# ccnor_stm32_v20.net
KiCad netlist of a schematic drawn in EAGLE
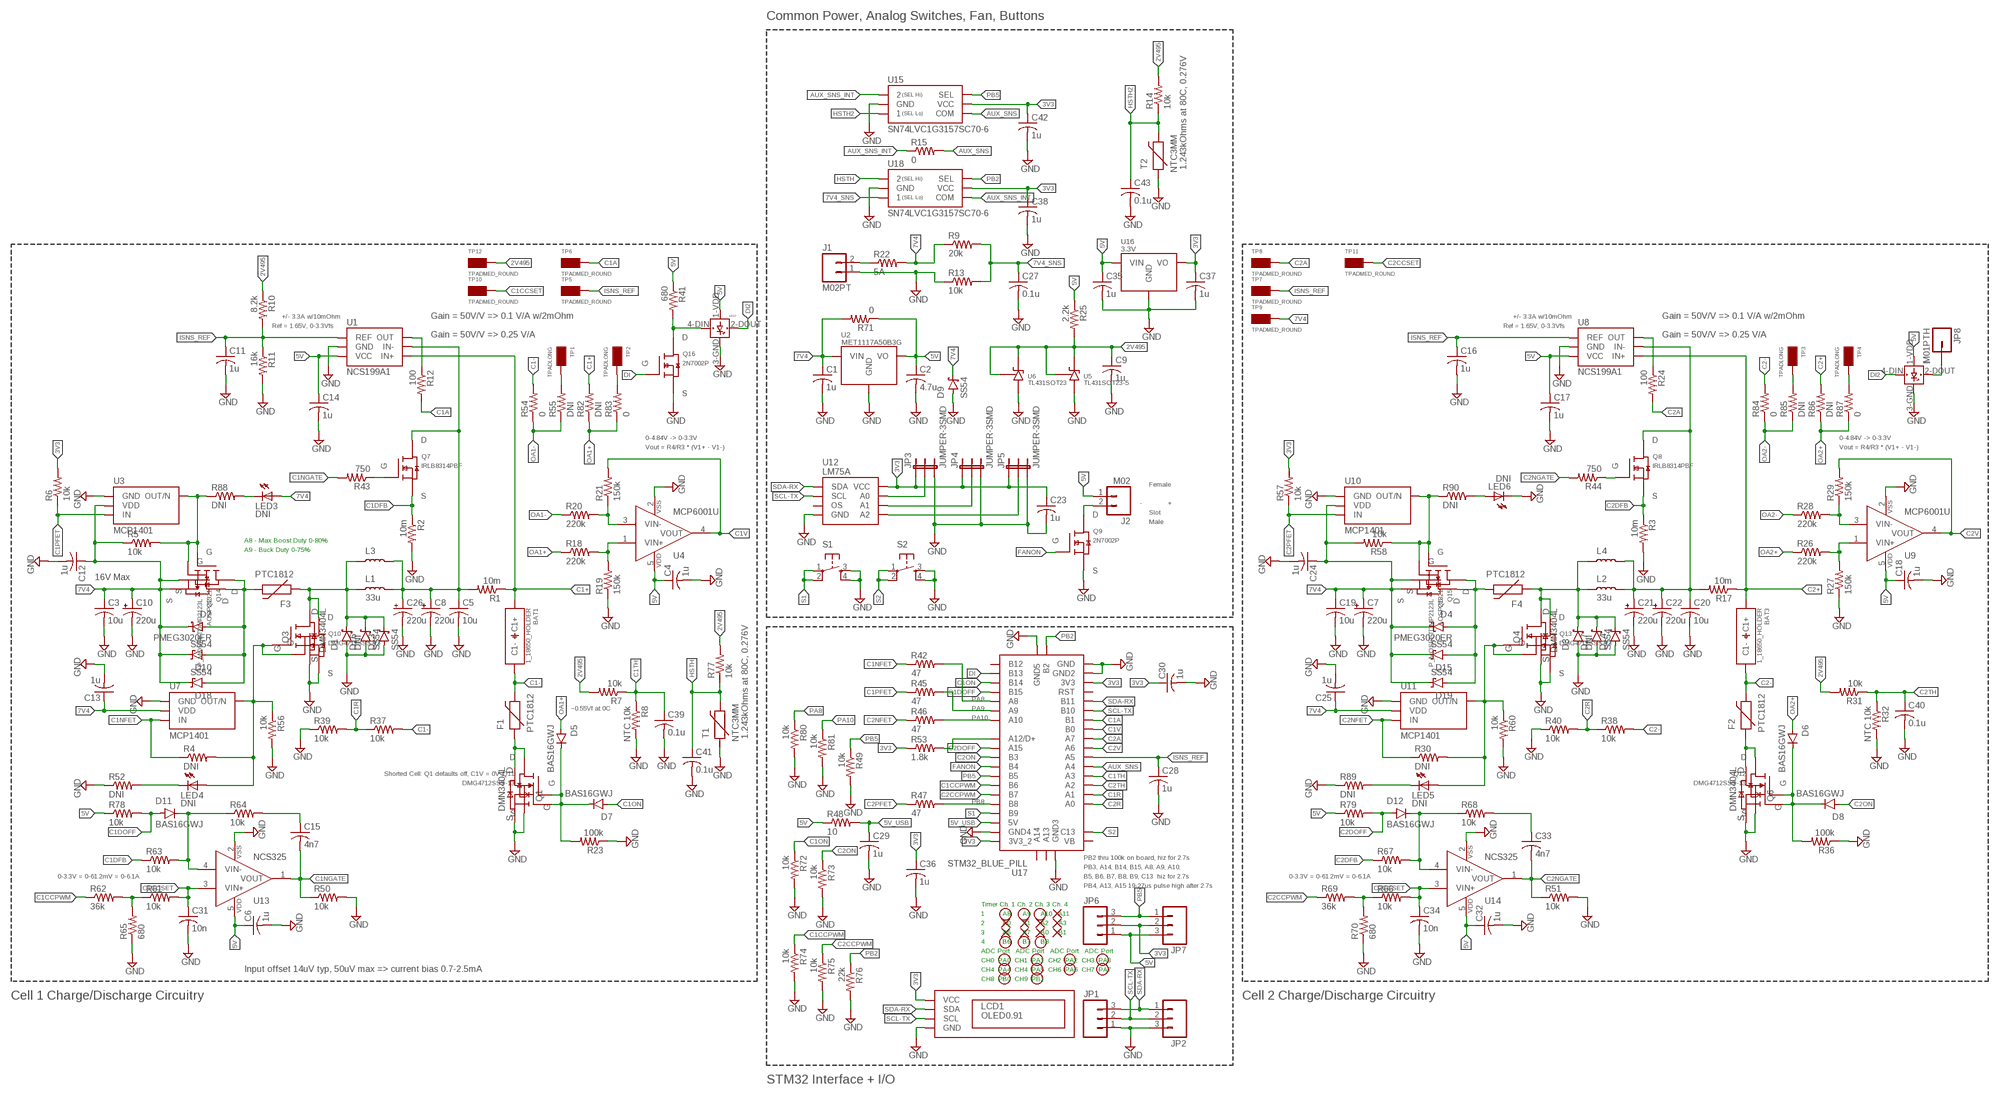
[diagram p0: schematic, sheet 1]

(export (version "E")
  (design (tool "Eeschema 10.0.6"))
  (components
    (comp (ref "BAT1")
      (value "1_18650_HOLDER")
      (footprint "eagle-import:1S_18650_SMD_NH")
      (libsource (lib "eagle-import") (part "1_18650_HOLDER"))
    )
    (comp (ref "BAT3")
      (value "1_18650_HOLDER")
      (footprint "eagle-import:1S_18650_SMD_NH")
      (libsource (lib "eagle-import") (part "1_18650_HOLDER"))
    )
    (comp (ref "C1")
      (value "1u")
      (footprint "eagle-import:C0402")
      (libsource (lib "eagle-import") (part "C-USC0402"))
    )
    (comp (ref "C2")
      (value "4.7u")
      (footprint "eagle-import:C0402")
      (libsource (lib "eagle-import") (part "C-USC0402"))
    )
    (comp (ref "C3")
      (value "10u")
      (footprint "eagle-import:C1206")
      (libsource (lib "eagle-import") (part "C-USC1206"))
    )
    (comp (ref "C4")
      (value "1u")
      (footprint "eagle-import:C0402")
      (libsource (lib "eagle-import") (part "C-USC0402"))
    )
    (comp (ref "C5")
      (value "10u")
      (footprint "eagle-import:C1206")
      (libsource (lib "eagle-import") (part "C-USC1206"))
    )
    (comp (ref "C6")
      (value "1u")
      (footprint "eagle-import:C0402")
      (libsource (lib "eagle-import") (part "C-USC0402"))
    )
    (comp (ref "C7")
      (value "220u")
      (footprint "eagle-import:PANASONIC_D")
      (libsource (lib "eagle-import") (part "CPOL-USD"))
    )
    (comp (ref "C8")
      (value "220u")
      (footprint "eagle-import:PANASONIC_D")
      (libsource (lib "eagle-import") (part "CPOL-USD"))
    )
    (comp (ref "C9")
      (value "1u")
      (footprint "eagle-import:C0402")
      (libsource (lib "eagle-import") (part "C-USC0402"))
    )
    (comp (ref "C10")
      (value "220u")
      (footprint "eagle-import:PANASONIC_D")
      (libsource (lib "eagle-import") (part "CPOL-USD"))
    )
    (comp (ref "C11")
      (value "1u")
      (footprint "eagle-import:C0402")
      (libsource (lib "eagle-import") (part "C-USC0402"))
    )
    (comp (ref "C12")
      (value "1u")
      (footprint "eagle-import:C0402")
      (libsource (lib "eagle-import") (part "C-USC0402"))
    )
    (comp (ref "C13")
      (value "1u")
      (footprint "eagle-import:C0402")
      (libsource (lib "eagle-import") (part "C-USC0402"))
    )
    (comp (ref "C14")
      (value "1u")
      (footprint "eagle-import:C0402")
      (libsource (lib "eagle-import") (part "C-USC0402"))
    )
    (comp (ref "C15")
      (value "4n7")
      (footprint "eagle-import:C0402")
      (libsource (lib "eagle-import") (part "C-USC0402"))
    )
    (comp (ref "C16")
      (value "1u")
      (footprint "eagle-import:C0402")
      (libsource (lib "eagle-import") (part "C-USC0402"))
    )
    (comp (ref "C17")
      (value "1u")
      (footprint "eagle-import:C0402")
      (libsource (lib "eagle-import") (part "C-USC0402"))
    )
    (comp (ref "C18")
      (value "1u")
      (footprint "eagle-import:C0402")
      (libsource (lib "eagle-import") (part "C-USC0402"))
    )
    (comp (ref "C19")
      (value "10u")
      (footprint "eagle-import:C1206")
      (libsource (lib "eagle-import") (part "C-USC1206"))
    )
    (comp (ref "C20")
      (value "10u")
      (footprint "eagle-import:C1206")
      (libsource (lib "eagle-import") (part "C-USC1206"))
    )
    (comp (ref "C21")
      (value "220u")
      (footprint "eagle-import:PANASONIC_D")
      (libsource (lib "eagle-import") (part "CPOL-USD"))
    )
    (comp (ref "C22")
      (value "220u")
      (footprint "eagle-import:PANASONIC_D")
      (libsource (lib "eagle-import") (part "CPOL-USD"))
    )
    (comp (ref "C23")
      (value "1u")
      (footprint "eagle-import:C0402")
      (libsource (lib "eagle-import") (part "C-USC0402"))
    )
    (comp (ref "C24")
      (value "1u")
      (footprint "eagle-import:C0402")
      (libsource (lib "eagle-import") (part "C-USC0402"))
    )
    (comp (ref "C25")
      (value "1u")
      (footprint "eagle-import:C0402")
      (libsource (lib "eagle-import") (part "C-USC0402"))
    )
    (comp (ref "C26")
      (value "220u")
      (footprint "eagle-import:PANASONIC_D")
      (libsource (lib "eagle-import") (part "CPOL-USD"))
    )
    (comp (ref "C27")
      (value "0.1u")
      (footprint "eagle-import:C0402")
      (libsource (lib "eagle-import") (part "C-USC0402"))
    )
    (comp (ref "C28")
      (value "1u")
      (footprint "eagle-import:C0402")
      (libsource (lib "eagle-import") (part "C-USC0402"))
    )
    (comp (ref "C29")
      (value "1u")
      (footprint "eagle-import:C0402")
      (libsource (lib "eagle-import") (part "C-USC0402"))
    )
    (comp (ref "C30")
      (value "1u")
      (footprint "eagle-import:C0402")
      (libsource (lib "eagle-import") (part "C-USC0402"))
    )
    (comp (ref "C31")
      (value "10n")
      (footprint "eagle-import:C0402")
      (libsource (lib "eagle-import") (part "C-USC0402"))
    )
    (comp (ref "C32")
      (value "1u")
      (footprint "eagle-import:C0402")
      (libsource (lib "eagle-import") (part "C-USC0402"))
    )
    (comp (ref "C33")
      (value "4n7")
      (footprint "eagle-import:C0402")
      (libsource (lib "eagle-import") (part "C-USC0402"))
    )
    (comp (ref "C34")
      (value "10n")
      (footprint "eagle-import:C0402")
      (libsource (lib "eagle-import") (part "C-USC0402"))
    )
    (comp (ref "C35")
      (value "1u")
      (footprint "eagle-import:C0402")
      (libsource (lib "eagle-import") (part "C-USC0402"))
    )
    (comp (ref "C36")
      (value "1u")
      (footprint "eagle-import:C0402")
      (libsource (lib "eagle-import") (part "C-USC0402"))
    )
    (comp (ref "C37")
      (value "1u")
      (footprint "eagle-import:C0402")
      (libsource (lib "eagle-import") (part "C-USC0402"))
    )
    (comp (ref "C38")
      (value "1u")
      (footprint "eagle-import:C0402")
      (libsource (lib "eagle-import") (part "C-USC0402"))
    )
    (comp (ref "C39")
      (value "0.1u")
      (footprint "eagle-import:C0402")
      (libsource (lib "eagle-import") (part "C-USC0402"))
    )
    (comp (ref "C40")
      (value "0.1u")
      (footprint "eagle-import:C0402")
      (libsource (lib "eagle-import") (part "C-USC0402"))
    )
    (comp (ref "C41")
      (value "0.1u")
      (footprint "eagle-import:C0402")
      (libsource (lib "eagle-import") (part "C-USC0402"))
    )
    (comp (ref "C42")
      (value "1u")
      (footprint "eagle-import:C0402")
      (libsource (lib "eagle-import") (part "C-USC0402"))
    )
    (comp (ref "C43")
      (value "0.1u")
      (footprint "eagle-import:C0402")
      (libsource (lib "eagle-import") (part "C-USC0402"))
    )
    (comp (ref "D1")
      (value "DNI")
      (footprint "eagle-import:SOD123W")
      (libsource (lib "eagle-import") (part "PMEG3020ER"))
    )
    (comp (ref "D2")
      (value "PMEG3020ER")
      (footprint "eagle-import:SOD123W")
      (libsource (lib "eagle-import") (part "PMEG3020ER"))
    )
    (comp (ref "D3")
      (value "DNI")
      (footprint "eagle-import:SOD123W")
      (libsource (lib "eagle-import") (part "PMEG3020ER"))
    )
    (comp (ref "D4")
      (value "PMEG3020ER")
      (footprint "eagle-import:SOD123W")
      (libsource (lib "eagle-import") (part "PMEG3020ER"))
    )
    (comp (ref "D5")
      (value "BAS16GWJ")
      (footprint "eagle-import:SOD323")
      (libsource (lib "eagle-import") (part "BAT60A"))
    )
    (comp (ref "D6")
      (value "BAS16GWJ")
      (footprint "eagle-import:SOD323")
      (libsource (lib "eagle-import") (part "BAT60A"))
    )
    (comp (ref "D7")
      (value "BAS16GWJ")
      (footprint "eagle-import:SOD323")
      (libsource (lib "eagle-import") (part "BAT60A"))
    )
    (comp (ref "D8")
      (value "BAS16GWJ")
      (footprint "eagle-import:SOD323")
      (libsource (lib "eagle-import") (part "BAT60A"))
    )
    (comp (ref "D9")
      (value "SS54")
      (footprint "eagle-import:SMA")
      (libsource (lib "eagle-import") (part "SS54"))
    )
    (comp (ref "D10")
      (value "SS54")
      (footprint "eagle-import:SMA")
      (libsource (lib "eagle-import") (part "SS54"))
    )
    (comp (ref "D11")
      (value "BAS16GWJ")
      (footprint "eagle-import:SOD323")
      (libsource (lib "eagle-import") (part "BAT60A"))
    )
    (comp (ref "D12")
      (value "BAS16GWJ")
      (footprint "eagle-import:SOD323")
      (libsource (lib "eagle-import") (part "BAT60A"))
    )
    (comp (ref "D13")
      (value "SS54")
      (footprint "eagle-import:SMA")
      (libsource (lib "eagle-import") (part "SS54"))
    )
    (comp (ref "D14")
      (value "SS54")
      (footprint "eagle-import:SMA")
      (libsource (lib "eagle-import") (part "SS54"))
    )
    (comp (ref "D15")
      (value "SS54")
      (footprint "eagle-import:SMA")
      (libsource (lib "eagle-import") (part "SS54"))
    )
    (comp (ref "D16")
      (value "SS54")
      (footprint "eagle-import:SMA")
      (libsource (lib "eagle-import") (part "SS54"))
    )
    (comp (ref "D17")
      (value "SS54")
      (footprint "eagle-import:SMA")
      (libsource (lib "eagle-import") (part "SS54"))
    )
    (comp (ref "D18")
      (value "SS54")
      (footprint "eagle-import:SMA")
      (libsource (lib "eagle-import") (part "SS54"))
    )
    (comp (ref "D19")
      (value "SS54")
      (footprint "eagle-import:SMA")
      (libsource (lib "eagle-import") (part "SS54"))
    )
    (comp (ref "F1")
      (value "PTC1812")
      (footprint "eagle-import:1812")
      (libsource (lib "eagle-import") (part "PTC1812"))
    )
    (comp (ref "F2")
      (value "PTC1812")
      (footprint "eagle-import:1812")
      (libsource (lib "eagle-import") (part "PTC1812"))
    )
    (comp (ref "F3")
      (value "PTC1812")
      (footprint "eagle-import:1812")
      (libsource (lib "eagle-import") (part "PTC1812"))
    )
    (comp (ref "F4")
      (value "PTC1812")
      (footprint "eagle-import:1812")
      (libsource (lib "eagle-import") (part "PTC1812"))
    )
    (comp (ref "J1")
      (value "M02PT")
      (footprint "eagle-import:PHOENIXCONTACT1935161")
      (libsource (lib "eagle-import") (part "M02PT"))
    )
    (comp (ref "J2")
      (value "M02")
      (footprint "eagle-import:B2B-XH-A")
      (libsource (lib "eagle-import") (part "M02"))
    )
    (comp (ref "JP1")
      (value "M03PTH")
      (footprint "eagle-import:1X03")
      (libsource (lib "eagle-import") (part "M03PTH"))
    )
    (comp (ref "JP2")
      (value "M03PTH")
      (footprint "eagle-import:1X03")
      (libsource (lib "eagle-import") (part "M03PTH"))
    )
    (comp (ref "JP3")
      (value "JUMPER-3SMD")
      (footprint "eagle-import:SJ_3")
      (libsource (lib "eagle-import") (part "JUMPER-3SMD"))
    )
    (comp (ref "JP4")
      (value "JUMPER-3SMD")
      (footprint "eagle-import:SJ_3")
      (libsource (lib "eagle-import") (part "JUMPER-3SMD"))
    )
    (comp (ref "JP5")
      (value "JUMPER-3SMD")
      (footprint "eagle-import:SJ_3")
      (libsource (lib "eagle-import") (part "JUMPER-3SMD"))
    )
    (comp (ref "JP6")
      (value "M03PTH")
      (footprint "eagle-import:1X03")
      (libsource (lib "eagle-import") (part "M03PTH"))
    )
    (comp (ref "JP7")
      (value "M03PTH")
      (footprint "eagle-import:1X03")
      (libsource (lib "eagle-import") (part "M03PTH"))
    )
    (comp (ref "JP8")
      (value "M01PTH")
      (footprint "eagle-import:1X01")
      (libsource (lib "eagle-import") (part "M01PTH"))
    )
    (comp (ref "L1")
      (value "33u")
      (footprint "eagle-import:INDUCTOR_SMD_13MM")
      (libsource (lib "eagle-import") (part "SDR1307"))
    )
    (comp (ref "L2")
      (value "33u")
      (footprint "eagle-import:INDUCTOR_SMD_13MM")
      (libsource (lib "eagle-import") (part "SDR1307"))
    )
    (comp (ref "L3")
      (value "INDUCTOR6A-LG")
      (footprint "eagle-import:INDUCTOR_6A_8MMX15MM")
      (libsource (lib "eagle-import") (part "INDUCTOR6A-LG"))
    )
    (comp (ref "L4")
      (value "INDUCTOR6A-LG")
      (footprint "eagle-import:INDUCTOR_6A_8MMX15MM")
      (libsource (lib "eagle-import") (part "INDUCTOR6A-LG"))
    )
    (comp (ref "LCD1")
      (value "OLED0.91")
      (footprint "eagle-import:OLED0.91")
      (libsource (lib "eagle-import") (part "OLED0.91"))
    )
    (comp (ref "LED3")
      (value "DNI")
      (footprint "eagle-import:CHIPLED_0603")
      (libsource (lib "eagle-import") (part "LEDCHIPLED_0603"))
    )
    (comp (ref "LED4")
      (value "DNI")
      (footprint "eagle-import:CHIPLED_0603")
      (libsource (lib "eagle-import") (part "LEDCHIPLED_0603"))
    )
    (comp (ref "LED5")
      (value "DNI")
      (footprint "eagle-import:CHIPLED_0603")
      (libsource (lib "eagle-import") (part "LEDCHIPLED_0603"))
    )
    (comp (ref "LED6")
      (value "DNI")
      (footprint "eagle-import:CHIPLED_0603")
      (libsource (lib "eagle-import") (part "LEDCHIPLED_0603"))
    )
    (comp (ref "LED7")
      (value "WS2812B")
      (footprint "eagle-import:WS2812B")
      (libsource (lib "eagle-import") (part "WS2812B"))
    )
    (comp (ref "LED8")
      (value "WS2812B")
      (footprint "eagle-import:WS2812B")
      (libsource (lib "eagle-import") (part "WS2812B"))
    )
    (comp (ref "Q1")
      (value "DMN3404L")
      (footprint "eagle-import:SOT23")
      (libsource (lib "eagle-import") (part "DMN3404L"))
    )
    (comp (ref "Q2")
      (value "P_MOSFETDMP2123L")
      (footprint "eagle-import:SOT23")
      (libsource (lib "eagle-import") (part "P_MOSFETDMP2123L"))
    )
    (comp (ref "Q3")
      (value "DMN3404L")
      (footprint "eagle-import:SOT23")
      (libsource (lib "eagle-import") (part "DMN3404L"))
    )
    (comp (ref "Q4")
      (value "DMN3404L")
      (footprint "eagle-import:SOT23")
      (libsource (lib "eagle-import") (part "DMN3404L"))
    )
    (comp (ref "Q5")
      (value "P_MOSFETDMP2123L")
      (footprint "eagle-import:SOT23")
      (libsource (lib "eagle-import") (part "P_MOSFETDMP2123L"))
    )
    (comp (ref "Q6")
      (value "DMN3404L")
      (footprint "eagle-import:SOT23")
      (libsource (lib "eagle-import") (part "DMN3404L"))
    )
    (comp (ref "Q7")
      (value "IRLB8314PBF")
      (footprint "eagle-import:TO-220")
      (libsource (lib "eagle-import") (part "IRLB8314PBF"))
    )
    (comp (ref "Q8")
      (value "IRLB8314PBF")
      (footprint "eagle-import:TO-220")
      (libsource (lib "eagle-import") (part "IRLB8314PBF"))
    )
    (comp (ref "Q9")
      (value "2N7002P")
      (footprint "eagle-import:SOT23")
      (libsource (lib "eagle-import") (part "2N7002P"))
    )
    (comp (ref "Q10")
      (value "DMG4712SSS-13")
      (footprint "eagle-import:8-SOIC")
      (libsource (lib "eagle-import") (part "N-MOSFET-SOIC8"))
    )
    (comp (ref "Q11")
      (value "DMG4712SSS-13")
      (footprint "eagle-import:8-SOIC")
      (libsource (lib "eagle-import") (part "N-MOSFET-SOIC8"))
    )
    (comp (ref "Q12")
      (value "DMG4712SSS-13")
      (footprint "eagle-import:8-SOIC")
      (libsource (lib "eagle-import") (part "N-MOSFET-SOIC8"))
    )
    (comp (ref "Q13")
      (value "DMG4712SSS-13")
      (footprint "eagle-import:8-SOIC")
      (libsource (lib "eagle-import") (part "N-MOSFET-SOIC8"))
    )
    (comp (ref "Q14")
      (value "AOSP21321")
      (footprint "eagle-import:8-SOIC")
      (libsource (lib "eagle-import") (part "P-MOSFET-SOIC8"))
    )
    (comp (ref "Q15")
      (value "AOSP21321")
      (footprint "eagle-import:8-SOIC")
      (libsource (lib "eagle-import") (part "P-MOSFET-SOIC8"))
    )
    (comp (ref "Q16")
      (value "2N7002P")
      (footprint "eagle-import:SOT23")
      (libsource (lib "eagle-import") (part "2N7002P"))
    )
    (comp (ref "R1")
      (value "10m")
      (footprint "eagle-import:R1206")
      (libsource (lib "eagle-import") (part "R-US_R1206"))
    )
    (comp (ref "R2")
      (value "10m")
      (footprint "eagle-import:R1206")
      (libsource (lib "eagle-import") (part "R-US_R1206"))
    )
    (comp (ref "R3")
      (value "10m")
      (footprint "eagle-import:R1206")
      (libsource (lib "eagle-import") (part "R-US_R1206"))
    )
    (comp (ref "R4")
      (value "DNI")
      (footprint "eagle-import:R0402")
      (libsource (lib "eagle-import") (part "R-US_R0402"))
    )
    (comp (ref "R5")
      (value "10k")
      (footprint "eagle-import:R0402")
      (libsource (lib "eagle-import") (part "R-US_R0402"))
    )
    (comp (ref "R6")
      (value "10k")
      (footprint "eagle-import:R0402")
      (libsource (lib "eagle-import") (part "R-US_R0402"))
    )
    (comp (ref "R7")
      (value "10k")
      (footprint "eagle-import:R0402")
      (libsource (lib "eagle-import") (part "R-US_R0402"))
    )
    (comp (ref "R8")
      (value "NTC 10k")
      (footprint "eagle-import:R0402")
      (libsource (lib "eagle-import") (part "R-US_R0402"))
    )
    (comp (ref "R9")
      (value "20k")
      (footprint "eagle-import:R0402")
      (libsource (lib "eagle-import") (part "R-US_R0402"))
    )
    (comp (ref "R10")
      (value "8.2k")
      (footprint "eagle-import:R0402")
      (libsource (lib "eagle-import") (part "R-US_R0402"))
    )
    (comp (ref "R11")
      (value "16k")
      (footprint "eagle-import:R0402")
      (libsource (lib "eagle-import") (part "R-US_R0402"))
    )
    (comp (ref "R12")
      (value "100")
      (footprint "eagle-import:R0402")
      (libsource (lib "eagle-import") (part "R-US_R0402"))
    )
    (comp (ref "R13")
      (value "10k")
      (footprint "eagle-import:R0402")
      (libsource (lib "eagle-import") (part "R-US_R0402"))
    )
    (comp (ref "R14")
      (value "10k")
      (footprint "eagle-import:R0402")
      (libsource (lib "eagle-import") (part "R-US_R0402"))
    )
    (comp (ref "R15")
      (value "0")
      (footprint "eagle-import:R0402")
      (libsource (lib "eagle-import") (part "R-US_R0402"))
    )
    (comp (ref "R17")
      (value "10m")
      (footprint "eagle-import:R1206")
      (libsource (lib "eagle-import") (part "R-US_R1206"))
    )
    (comp (ref "R18")
      (value "220k")
      (footprint "eagle-import:R0402")
      (libsource (lib "eagle-import") (part "R-US_R0402"))
    )
    (comp (ref "R19")
      (value "150k")
      (footprint "eagle-import:R0402")
      (libsource (lib "eagle-import") (part "R-US_R0402"))
    )
    (comp (ref "R20")
      (value "220k")
      (footprint "eagle-import:R0402")
      (libsource (lib "eagle-import") (part "R-US_R0402"))
    )
    (comp (ref "R21")
      (value "150k")
      (footprint "eagle-import:R0402")
      (libsource (lib "eagle-import") (part "R-US_R0402"))
    )
    (comp (ref "R22")
      (value "5A")
      (footprint "eagle-import:R1206")
      (libsource (lib "eagle-import") (part "R-US_R1206"))
    )
    (comp (ref "R23")
      (value "100k")
      (footprint "eagle-import:R0402")
      (libsource (lib "eagle-import") (part "R-US_R0402"))
    )
    (comp (ref "R24")
      (value "100")
      (footprint "eagle-import:R0402")
      (libsource (lib "eagle-import") (part "R-US_R0402"))
    )
    (comp (ref "R25")
      (value "2.2k")
      (footprint "eagle-import:R0402")
      (libsource (lib "eagle-import") (part "R-US_R0402"))
    )
    (comp (ref "R26")
      (value "220k")
      (footprint "eagle-import:R0402")
      (libsource (lib "eagle-import") (part "R-US_R0402"))
    )
    (comp (ref "R27")
      (value "150k")
      (footprint "eagle-import:R0402")
      (libsource (lib "eagle-import") (part "R-US_R0402"))
    )
    (comp (ref "R28")
      (value "220k")
      (footprint "eagle-import:R0402")
      (libsource (lib "eagle-import") (part "R-US_R0402"))
    )
    (comp (ref "R29")
      (value "150k")
      (footprint "eagle-import:R0402")
      (libsource (lib "eagle-import") (part "R-US_R0402"))
    )
    (comp (ref "R30")
      (value "DNI")
      (footprint "eagle-import:R0402")
      (libsource (lib "eagle-import") (part "R-US_R0402"))
    )
    (comp (ref "R31")
      (value "10k")
      (footprint "eagle-import:R0402")
      (libsource (lib "eagle-import") (part "R-US_R0402"))
    )
    (comp (ref "R32")
      (value "NTC 10k")
      (footprint "eagle-import:R0402")
      (libsource (lib "eagle-import") (part "R-US_R0402"))
    )
    (comp (ref "R36")
      (value "100k")
      (footprint "eagle-import:R0402")
      (libsource (lib "eagle-import") (part "R-US_R0402"))
    )
    (comp (ref "R37")
      (value "10k")
      (footprint "eagle-import:R0402")
      (libsource (lib "eagle-import") (part "R-US_R0402"))
    )
    (comp (ref "R38")
      (value "10k")
      (footprint "eagle-import:R0402")
      (libsource (lib "eagle-import") (part "R-US_R0402"))
    )
    (comp (ref "R39")
      (value "10k")
      (footprint "eagle-import:R0402")
      (libsource (lib "eagle-import") (part "R-US_R0402"))
    )
    (comp (ref "R40")
      (value "10k")
      (footprint "eagle-import:R0402")
      (libsource (lib "eagle-import") (part "R-US_R0402"))
    )
    (comp (ref "R41")
      (value "680")
      (footprint "eagle-import:R0402")
      (libsource (lib "eagle-import") (part "R-US_R0402"))
    )
    (comp (ref "R42")
      (value "47")
      (footprint "eagle-import:R0402")
      (libsource (lib "eagle-import") (part "R-US_R0402"))
    )
    (comp (ref "R43")
      (value "750")
      (footprint "eagle-import:R0402")
      (libsource (lib "eagle-import") (part "R-US_R0402"))
    )
    (comp (ref "R44")
      (value "750")
      (footprint "eagle-import:R0402")
      (libsource (lib "eagle-import") (part "R-US_R0402"))
    )
    (comp (ref "R45")
      (value "47")
      (footprint "eagle-import:R0402")
      (libsource (lib "eagle-import") (part "R-US_R0402"))
    )
    (comp (ref "R46")
      (value "47")
      (footprint "eagle-import:R0402")
      (libsource (lib "eagle-import") (part "R-US_R0402"))
    )
    (comp (ref "R47")
      (value "47")
      (footprint "eagle-import:R0402")
      (libsource (lib "eagle-import") (part "R-US_R0402"))
    )
    (comp (ref "R48")
      (value "10")
      (footprint "eagle-import:R0402")
      (libsource (lib "eagle-import") (part "R-US_R0402"))
    )
    (comp (ref "R49")
      (value "10k")
      (footprint "eagle-import:R0402")
      (libsource (lib "eagle-import") (part "R-US_R0402"))
    )
    (comp (ref "R50")
      (value "10k")
      (footprint "eagle-import:R0402")
      (libsource (lib "eagle-import") (part "R-US_R0402"))
    )
    (comp (ref "R51")
      (value "10k")
      (footprint "eagle-import:R0402")
      (libsource (lib "eagle-import") (part "R-US_R0402"))
    )
    (comp (ref "R52")
      (value "DNI")
      (footprint "eagle-import:R0402")
      (libsource (lib "eagle-import") (part "R-US_R0402"))
    )
    (comp (ref "R53")
      (value "1.8k")
      (footprint "eagle-import:R0402")
      (libsource (lib "eagle-import") (part "R-US_R0402"))
    )
    (comp (ref "R54")
      (value "0")
      (footprint "eagle-import:R0402")
      (libsource (lib "eagle-import") (part "R-US_R0402"))
    )
    (comp (ref "R55")
      (value "DNI")
      (footprint "eagle-import:R0402")
      (libsource (lib "eagle-import") (part "R-US_R0402"))
    )
    (comp (ref "R56")
      (value "10k")
      (footprint "eagle-import:R0402")
      (libsource (lib "eagle-import") (part "R-US_R0402"))
    )
    (comp (ref "R57")
      (value "10k")
      (footprint "eagle-import:R0402")
      (libsource (lib "eagle-import") (part "R-US_R0402"))
    )
    (comp (ref "R58")
      (value "10k")
      (footprint "eagle-import:R0402")
      (libsource (lib "eagle-import") (part "R-US_R0402"))
    )
    (comp (ref "R60")
      (value "10k")
      (footprint "eagle-import:R0402")
      (libsource (lib "eagle-import") (part "R-US_R0402"))
    )
    (comp (ref "R61")
      (value "10k")
      (footprint "eagle-import:R0402")
      (libsource (lib "eagle-import") (part "R-US_R0402"))
    )
    (comp (ref "R62")
      (value "36k")
      (footprint "eagle-import:R0402")
      (libsource (lib "eagle-import") (part "R-US_R0402"))
    )
    (comp (ref "R63")
      (value "10k")
      (footprint "eagle-import:R0402")
      (libsource (lib "eagle-import") (part "R-US_R0402"))
    )
    (comp (ref "R64")
      (value "10k")
      (footprint "eagle-import:R0402")
      (libsource (lib "eagle-import") (part "R-US_R0402"))
    )
    (comp (ref "R65")
      (value "680")
      (footprint "eagle-import:R0402")
      (libsource (lib "eagle-import") (part "R-US_R0402"))
    )
    (comp (ref "R66")
      (value "10k")
      (footprint "eagle-import:R0402")
      (libsource (lib "eagle-import") (part "R-US_R0402"))
    )
    (comp (ref "R67")
      (value "10k")
      (footprint "eagle-import:R0402")
      (libsource (lib "eagle-import") (part "R-US_R0402"))
    )
    (comp (ref "R68")
      (value "10k")
      (footprint "eagle-import:R0402")
      (libsource (lib "eagle-import") (part "R-US_R0402"))
    )
    (comp (ref "R69")
      (value "36k")
      (footprint "eagle-import:R0402")
      (libsource (lib "eagle-import") (part "R-US_R0402"))
    )
    (comp (ref "R70")
      (value "680")
      (footprint "eagle-import:R0402")
      (libsource (lib "eagle-import") (part "R-US_R0402"))
    )
    (comp (ref "R71")
      (value "0")
      (footprint "eagle-import:R0603")
      (libsource (lib "eagle-import") (part "R-US_R0603"))
    )
    (comp (ref "R72")
      (value "10k")
      (footprint "eagle-import:R0402")
      (libsource (lib "eagle-import") (part "R-US_R0402"))
    )
    (comp (ref "R73")
      (value "10k")
      (footprint "eagle-import:R0402")
      (libsource (lib "eagle-import") (part "R-US_R0402"))
    )
    (comp (ref "R74")
      (value "10k")
      (footprint "eagle-import:R0402")
      (libsource (lib "eagle-import") (part "R-US_R0402"))
    )
    (comp (ref "R75")
      (value "10k")
      (footprint "eagle-import:R0402")
      (libsource (lib "eagle-import") (part "R-US_R0402"))
    )
    (comp (ref "R76")
      (value "22k")
      (footprint "eagle-import:R0402")
      (libsource (lib "eagle-import") (part "R-US_R0402"))
    )
    (comp (ref "R77")
      (value "10k")
      (footprint "eagle-import:R0402")
      (libsource (lib "eagle-import") (part "R-US_R0402"))
    )
    (comp (ref "R78")
      (value "10k")
      (footprint "eagle-import:R0402")
      (libsource (lib "eagle-import") (part "R-US_R0402"))
    )
    (comp (ref "R79")
      (value "10k")
      (footprint "eagle-import:R0402")
      (libsource (lib "eagle-import") (part "R-US_R0402"))
    )
    (comp (ref "R80")
      (value "10k")
      (footprint "eagle-import:R0402")
      (libsource (lib "eagle-import") (part "R-US_R0402"))
    )
    (comp (ref "R81")
      (value "10k")
      (footprint "eagle-import:R0402")
      (libsource (lib "eagle-import") (part "R-US_R0402"))
    )
    (comp (ref "R82")
      (value "DNI")
      (footprint "eagle-import:R0402")
      (libsource (lib "eagle-import") (part "R-US_R0402"))
    )
    (comp (ref "R83")
      (value "0")
      (footprint "eagle-import:R0402")
      (libsource (lib "eagle-import") (part "R-US_R0402"))
    )
    (comp (ref "R84")
      (value "0")
      (footprint "eagle-import:R0402")
      (libsource (lib "eagle-import") (part "R-US_R0402"))
    )
    (comp (ref "R85")
      (value "DNI")
      (footprint "eagle-import:R0402")
      (libsource (lib "eagle-import") (part "R-US_R0402"))
    )
    (comp (ref "R86")
      (value "DNI")
      (footprint "eagle-import:R0402")
      (libsource (lib "eagle-import") (part "R-US_R0402"))
    )
    (comp (ref "R87")
      (value "0")
      (footprint "eagle-import:R0402")
      (libsource (lib "eagle-import") (part "R-US_R0402"))
    )
    (comp (ref "R88")
      (value "DNI")
      (footprint "eagle-import:R0402")
      (libsource (lib "eagle-import") (part "R-US_R0402"))
    )
    (comp (ref "R89")
      (value "DNI")
      (footprint "eagle-import:R0402")
      (libsource (lib "eagle-import") (part "R-US_R0402"))
    )
    (comp (ref "R90")
      (value "DNI")
      (footprint "eagle-import:R0402")
      (libsource (lib "eagle-import") (part "R-US_R0402"))
    )
    (comp (ref "S1")
      (value "TAC_SWITCHSMD")
      (footprint "eagle-import:TACTILE_SWITCH_SMD")
      (libsource (lib "eagle-import") (part "TAC_SWITCHSMD"))
    )
    (comp (ref "S2")
      (value "TAC_SWITCHSMD")
      (footprint "eagle-import:TACTILE_SWITCH_SMD")
      (libsource (lib "eagle-import") (part "TAC_SWITCHSMD"))
    )
    (comp (ref "T1")
      (value "NTC3MM")
      (footprint "eagle-import:THERMISTOR_3MMX3MM")
      (libsource (lib "eagle-import") (part "PTCNTC3MM"))
    )
    (comp (ref "T2")
      (value "NTC3MM")
      (footprint "eagle-import:THERMISTOR_3MMX3MM")
      (libsource (lib "eagle-import") (part "PTCNTC3MM"))
    )
    (comp (ref "TP1")
      (value "TPADLONG")
      (footprint "eagle-import:TPAD_LONG")
      (libsource (lib "eagle-import") (part "TPADLONG"))
    )
    (comp (ref "TP2")
      (value "TPADLONG")
      (footprint "eagle-import:TPAD_LONG")
      (libsource (lib "eagle-import") (part "TPADLONG"))
    )
    (comp (ref "TP3")
      (value "TPADLONG")
      (footprint "eagle-import:TPAD_LONG")
      (libsource (lib "eagle-import") (part "TPADLONG"))
    )
    (comp (ref "TP4")
      (value "TPADLONG")
      (footprint "eagle-import:TPAD_LONG")
      (libsource (lib "eagle-import") (part "TPADLONG"))
    )
    (comp (ref "TP5")
      (value "TPADMED_ROUND")
      (footprint "eagle-import:TPAD_MED_ROUND")
      (libsource (lib "eagle-import") (part "TPADMED_ROUND"))
    )
    (comp (ref "TP6")
      (value "TPADMED_ROUND")
      (footprint "eagle-import:TPAD_MED_ROUND")
      (libsource (lib "eagle-import") (part "TPADMED_ROUND"))
    )
    (comp (ref "TP7")
      (value "TPADMED_ROUND")
      (footprint "eagle-import:TPAD_MED_ROUND")
      (libsource (lib "eagle-import") (part "TPADMED_ROUND"))
    )
    (comp (ref "TP8")
      (value "TPADMED_ROUND")
      (footprint "eagle-import:TPAD_MED_ROUND")
      (libsource (lib "eagle-import") (part "TPADMED_ROUND"))
    )
    (comp (ref "TP9")
      (value "TPADMED_ROUND")
      (footprint "eagle-import:TPAD_MED_ROUND")
      (libsource (lib "eagle-import") (part "TPADMED_ROUND"))
    )
    (comp (ref "TP10")
      (value "TPADMED_ROUND")
      (footprint "eagle-import:TPAD_MED_ROUND")
      (libsource (lib "eagle-import") (part "TPADMED_ROUND"))
    )
    (comp (ref "TP11")
      (value "TPADMED_ROUND")
      (footprint "eagle-import:TPAD_MED_ROUND")
      (libsource (lib "eagle-import") (part "TPADMED_ROUND"))
    )
    (comp (ref "TP12")
      (value "TPADMED_ROUND")
      (footprint "eagle-import:TPAD_MED_ROUND")
      (libsource (lib "eagle-import") (part "TPADMED_ROUND"))
    )
    (comp (ref "U1")
      (value "NCS199A1")
      (footprint "eagle-import:SOT-363")
      (libsource (lib "eagle-import") (part "INA214"))
    )
    (comp (ref "U2")
      (value "MET1117A50B3G")
      (footprint "eagle-import:TO-261")
      (libsource (lib "eagle-import") (part "ZLDO1117"))
    )
    (comp (ref "U3")
      (value "MCP1401")
      (footprint "eagle-import:SOT23-5")
      (libsource (lib "eagle-import") (part "MCP1401"))
    )
    (comp (ref "U4")
      (value "MCP6001U")
      (footprint "eagle-import:SOT23-5")
      (libsource (lib "eagle-import") (part "MCP6001U"))
    )
    (comp (ref "U5")
      (value "TL431SOT23-5")
      (footprint "eagle-import:SOT23-5")
      (libsource (lib "eagle-import") (part "TL431SOT23-5"))
    )
    (comp (ref "U6")
      (value "TL431SOT23")
      (footprint "eagle-import:SOT23")
      (libsource (lib "eagle-import") (part "TL431SOT23"))
    )
    (comp (ref "U7")
      (value "MCP1401")
      (footprint "eagle-import:SOT23-5")
      (libsource (lib "eagle-import") (part "MCP1401"))
    )
    (comp (ref "U8")
      (value "NCS199A1")
      (footprint "eagle-import:SOT-363")
      (libsource (lib "eagle-import") (part "INA214"))
    )
    (comp (ref "U9")
      (value "MCP6001U")
      (footprint "eagle-import:SOT23-5")
      (libsource (lib "eagle-import") (part "MCP6001U"))
    )
    (comp (ref "U10")
      (value "MCP1401")
      (footprint "eagle-import:SOT23-5")
      (libsource (lib "eagle-import") (part "MCP1401"))
    )
    (comp (ref "U11")
      (value "MCP1401")
      (footprint "eagle-import:SOT23-5")
      (libsource (lib "eagle-import") (part "MCP1401"))
    )
    (comp (ref "U12")
      (value "LM75A")
      (footprint "eagle-import:8-SOIC")
      (libsource (lib "eagle-import") (part "LM75A"))
    )
    (comp (ref "U13")
      (value "NCS325")
      (footprint "eagle-import:SOT23-5")
      (libsource (lib "eagle-import") (part "NCS325"))
    )
    (comp (ref "U14")
      (value "NCS325")
      (footprint "eagle-import:SOT23-5")
      (libsource (lib "eagle-import") (part "NCS325"))
    )
    (comp (ref "U15")
      (value "SN74LVC1G3157SC70-6")
      (footprint "eagle-import:SC70-6")
      (libsource (lib "eagle-import") (part "SN74LVC1G3157SC70-6"))
    )
    (comp (ref "U16")
      (value "3.3V")
      (footprint "eagle-import:SOT-89")
      (libsource (lib "eagle-import") (part "AP1117UR133-B"))
    )
    (comp (ref "U17")
      (value "STM32_BLUE_PILL")
      (footprint "eagle-import:STM32_BLUE_PILL_USABLE")
      (libsource (lib "eagle-import") (part "STM32_BLUE_PILL"))
    )
    (comp (ref "U18")
      (value "SN74LVC1G3157SC70-6")
      (footprint "eagle-import:SC70-6")
      (libsource (lib "eagle-import") (part "SN74LVC1G3157SC70-6"))
    )
  )
  (nets
    (net (code "1") (name "/PA9") (class "Default")
      (node (ref "R45") (pin "2") (pinfunction "2_2") (pintype "passive"))
      (node (ref "U17") (pin "A9") (pinfunction "A9_A9") (pintype "bidirectional"))
    )
    (net (code "2") (name "/PB8") (class "Default")
      (node (ref "R47") (pin "2") (pinfunction "2_2") (pintype "passive"))
      (node (ref "U17") (pin "B8") (pinfunction "B8_B8") (pintype "bidirectional"))
    )
    (net (code "3") (name "2V495") (class "Default")
      (node (ref "C9") (pin "1") (pinfunction "1_1") (pintype "passive"))
      (node (ref "R10") (pin "1") (pinfunction "1_1") (pintype "passive"))
      (node (ref "R14") (pin "2") (pinfunction "2_2") (pintype "passive"))
      (node (ref "R25") (pin "2") (pinfunction "2_2") (pintype "passive"))
      (node (ref "R31") (pin "2") (pinfunction "2_2") (pintype "passive"))
      (node (ref "R7") (pin "2") (pinfunction "2_2") (pintype "passive"))
      (node (ref "R77") (pin "2") (pinfunction "2_2") (pintype "passive"))
      (node (ref "TP12") (pin "1") (pinfunction "1_1") (pintype "bidirectional"))
      (node (ref "U5") (pin "3") (pinfunction "K_3") (pintype "passive"))
      (node (ref "U5") (pin "4") (pinfunction "REF_4") (pintype "passive"))
      (node (ref "U6") (pin "1") (pinfunction "K_1") (pintype "passive"))
      (node (ref "U6") (pin "2") (pinfunction "REF_2") (pintype "passive"))
    )
    (net (code "4") (name "3V3") (class "Default")
      (node (ref "C23") (pin "1") (pinfunction "1_1") (pintype "passive"))
      (node (ref "C30") (pin "1") (pinfunction "1_1") (pintype "passive"))
      (node (ref "C36") (pin "1") (pinfunction "1_1") (pintype "passive"))
      (node (ref "C37") (pin "1") (pinfunction "1_1") (pintype "passive"))
      (node (ref "C38") (pin "1") (pinfunction "1_1") (pintype "passive"))
      (node (ref "C42") (pin "1") (pinfunction "1_1") (pintype "passive"))
      (node (ref "JP3") (pin "1") (pinfunction "1_1") (pintype "passive"))
      (node (ref "JP4") (pin "1") (pinfunction "1_1") (pintype "passive"))
      (node (ref "JP5") (pin "1") (pinfunction "1_1") (pintype "passive"))
      (node (ref "JP6") (pin "2") (pinfunction "2_2") (pintype "passive"))
      (node (ref "JP7") (pin "2") (pinfunction "2_2") (pintype "passive"))
      (node (ref "LCD1") (pin "2-VCC") (pinfunction "VCC_2-VCC") (pintype "bidirectional"))
      (node (ref "R53") (pin "1") (pinfunction "1_1") (pintype "passive"))
      (node (ref "R57") (pin "2") (pinfunction "2_2") (pintype "passive"))
      (node (ref "R6") (pin "2") (pinfunction "2_2") (pintype "passive"))
      (node (ref "U12") (pin "8") (pinfunction "VCC_8") (pintype "bidirectional"))
      (node (ref "U15") (pin "5") (pinfunction "VCC_5") (pintype "bidirectional"))
      (node (ref "U16") (pin "1") (pinfunction "VO_1") (pintype "bidirectional"))
      (node (ref "U17") (pin "3V3") (pinfunction "3V3_3V3") (pintype "bidirectional"))
      (node (ref "U17") (pin "3V3_2") (pinfunction "3V3_2_3V3_2") (pintype "bidirectional"))
      (node (ref "U18") (pin "5") (pinfunction "VCC_5") (pintype "bidirectional"))
    )
    (net (code "5") (name "5V") (class "Default")
      (node (ref "C14") (pin "1") (pinfunction "1_1") (pintype "passive"))
      (node (ref "C17") (pin "1") (pinfunction "1_1") (pintype "passive"))
      (node (ref "C18") (pin "1") (pinfunction "1_1") (pintype "passive"))
      (node (ref "C2") (pin "1") (pinfunction "1_1") (pintype "passive"))
      (node (ref "C32") (pin "1") (pinfunction "1_1") (pintype "passive"))
      (node (ref "C35") (pin "1") (pinfunction "1_1") (pintype "passive"))
      (node (ref "C4") (pin "1") (pinfunction "1_1") (pintype "passive"))
      (node (ref "C6") (pin "1") (pinfunction "1_1") (pintype "passive"))
      (node (ref "J2") (pin "1") (pinfunction "1_1") (pintype "passive"))
      (node (ref "JP6") (pin "1") (pinfunction "1_1") (pintype "passive"))
      (node (ref "JP7") (pin "3") (pinfunction "3_3") (pintype "passive"))
      (node (ref "LED7") (pin "1-VDD") (pinfunction "VDD_1-VDD") (pintype "bidirectional"))
      (node (ref "LED8") (pin "1-VDD") (pinfunction "VDD_1-VDD") (pintype "bidirectional"))
      (node (ref "R25") (pin "1") (pinfunction "1_1") (pintype "passive"))
      (node (ref "R41") (pin "1") (pinfunction "1_1") (pintype "passive"))
      (node (ref "R48") (pin "1") (pinfunction "1_1") (pintype "passive"))
      (node (ref "R71") (pin "1") (pinfunction "1_1") (pintype "passive"))
      (node (ref "R78") (pin "1") (pinfunction "1_1") (pintype "passive"))
      (node (ref "R79") (pin "1") (pinfunction "1_1") (pintype "passive"))
      (node (ref "U1") (pin "3") (pinfunction "VCC_3") (pintype "bidirectional"))
      (node (ref "U13") (pin "5") (pinfunction "VDD_5") (pintype "bidirectional"))
      (node (ref "U14") (pin "5") (pinfunction "VDD_5") (pintype "bidirectional"))
      (node (ref "U16") (pin "3") (pinfunction "VIN_3") (pintype "bidirectional"))
      (node (ref "U2") (pin "2") (pinfunction "VO_2") (pintype "bidirectional"))
      (node (ref "U2") (pin "4") (pinfunction "VO_4") (pintype "bidirectional"))
      (node (ref "U4") (pin "5") (pinfunction "VDD_5") (pintype "bidirectional"))
      (node (ref "U8") (pin "3") (pinfunction "VCC_3") (pintype "bidirectional"))
      (node (ref "U9") (pin "5") (pinfunction "VDD_5") (pintype "bidirectional"))
    )
    (net (code "6") (name "5V_USB") (class "Default")
      (node (ref "C29") (pin "1") (pinfunction "1_1") (pintype "passive"))
      (node (ref "R48") (pin "2") (pinfunction "2_2") (pintype "passive"))
      (node (ref "U17") (pin "5V") (pinfunction "5V_5V") (pintype "bidirectional"))
    )
    (net (code "7") (name "7V4") (class "Default")
      (node (ref "C1") (pin "1") (pinfunction "1_1") (pintype "passive"))
      (node (ref "C10") (pin "+") (pinfunction "+_+") (pintype "passive"))
      (node (ref "C12") (pin "1") (pinfunction "1_1") (pintype "passive"))
      (node (ref "C13") (pin "1") (pinfunction "1_1") (pintype "passive"))
      (node (ref "C19") (pin "1") (pinfunction "1_1") (pintype "passive"))
      (node (ref "C24") (pin "1") (pinfunction "1_1") (pintype "passive"))
      (node (ref "C25") (pin "1") (pinfunction "1_1") (pintype "passive"))
      (node (ref "C3") (pin "1") (pinfunction "1_1") (pintype "passive"))
      (node (ref "C7") (pin "+") (pinfunction "+_+") (pintype "passive"))
      (node (ref "D10") (pin "K") (pinfunction "CATHODE_K") (pintype "passive"))
      (node (ref "D15") (pin "K") (pinfunction "CATHODE_K") (pintype "passive"))
      (node (ref "D18") (pin "K") (pinfunction "CATHODE_K") (pintype "passive"))
      (node (ref "D19") (pin "K") (pinfunction "CATHODE_K") (pintype "passive"))
      (node (ref "D2") (pin "K") (pinfunction "CATHODE_K") (pintype "passive"))
      (node (ref "D4") (pin "K") (pinfunction "CATHODE_K") (pintype "passive"))
      (node (ref "D9") (pin "K") (pinfunction "CATHODE_K") (pintype "passive"))
      (node (ref "LED3") (pin "A") (pinfunction "A_A") (pintype "passive"))
      (node (ref "Q14") (pin "1") (pinfunction "S_1") (pintype "bidirectional"))
      (node (ref "Q14") (pin "2") (pinfunction "S_2") (pintype "bidirectional"))
      (node (ref "Q14") (pin "3") (pinfunction "S_3") (pintype "bidirectional"))
      (node (ref "Q15") (pin "1") (pinfunction "S_1") (pintype "bidirectional"))
      (node (ref "Q15") (pin "2") (pinfunction "S_2") (pintype "bidirectional"))
      (node (ref "Q15") (pin "3") (pinfunction "S_3") (pintype "bidirectional"))
      (node (ref "Q2") (pin "2") (pinfunction "S_2") (pintype "bidirectional"))
      (node (ref "Q5") (pin "2") (pinfunction "S_2") (pintype "bidirectional"))
      (node (ref "R22") (pin "2") (pinfunction "2_2") (pintype "passive"))
      (node (ref "R5") (pin "1") (pinfunction "1_1") (pintype "passive"))
      (node (ref "R58") (pin "2") (pinfunction "2_2") (pintype "passive"))
      (node (ref "R71") (pin "2") (pinfunction "2_2") (pintype "passive"))
      (node (ref "R9") (pin "1") (pinfunction "1_1") (pintype "passive"))
      (node (ref "TP9") (pin "1") (pinfunction "1_1") (pintype "bidirectional"))
      (node (ref "U10") (pin "2") (pinfunction "VDD_2") (pintype "bidirectional"))
      (node (ref "U11") (pin "2") (pinfunction "VDD_2") (pintype "bidirectional"))
      (node (ref "U2") (pin "3") (pinfunction "VIN_3") (pintype "bidirectional"))
      (node (ref "U3") (pin "2") (pinfunction "VDD_2") (pintype "bidirectional"))
      (node (ref "U7") (pin "2") (pinfunction "VDD_2") (pintype "bidirectional"))
    )
    (net (code "8") (name "7V4_SNS") (class "Default")
      (node (ref "C27") (pin "1") (pinfunction "1_1") (pintype "passive"))
      (node (ref "R13") (pin "2") (pinfunction "2_2") (pintype "passive"))
      (node (ref "R9") (pin "2") (pinfunction "2_2") (pintype "passive"))
      (node (ref "U18") (pin "3") (pinfunction "1_3") (pintype "bidirectional"))
    )
    (net (code "9") (name "AUX_SNS") (class "Default")
      (node (ref "R15") (pin "2") (pinfunction "2_2") (pintype "passive"))
      (node (ref "U15") (pin "4") (pinfunction "COM_4") (pintype "bidirectional"))
      (node (ref "U17") (pin "A4") (pinfunction "A4_A4") (pintype "bidirectional"))
    )
    (net (code "10") (name "AUX_SNS_INT") (class "Default")
      (node (ref "R15") (pin "1") (pinfunction "1_1") (pintype "passive"))
      (node (ref "U15") (pin "1") (pinfunction "2_1") (pintype "bidirectional"))
      (node (ref "U18") (pin "4") (pinfunction "COM_4") (pintype "bidirectional"))
    )
    (net (code "11") (name "C1+") (class "Default")
      (node (ref "BAT1") (pin "1+") (pinfunction "C1+_1+") (pintype "bidirectional"))
      (node (ref "R1") (pin "1") (pinfunction "1_1") (pintype "passive"))
      (node (ref "R82") (pin "2") (pinfunction "2_2") (pintype "passive"))
      (node (ref "U1") (pin "4") (pinfunction "IN+_4") (pintype "bidirectional"))
    )
    (net (code "12") (name "C1-") (class "Default")
      (node (ref "BAT1") (pin "1-") (pinfunction "C1-_1-") (pintype "bidirectional"))
      (node (ref "F1") (pin "2") (pinfunction "2_2") (pintype "bidirectional"))
      (node (ref "R37") (pin "2") (pinfunction "2_2") (pintype "passive"))
      (node (ref "R54") (pin "2") (pinfunction "2_2") (pintype "passive"))
    )
    (net (code "13") (name "C1A") (class "Default")
      (node (ref "R12") (pin "2") (pinfunction "2_2") (pintype "passive"))
      (node (ref "TP6") (pin "1") (pinfunction "1_1") (pintype "bidirectional"))
      (node (ref "U17") (pin "B1") (pinfunction "B1_B1") (pintype "bidirectional"))
    )
    (net (code "14") (name "C1CCPWM") (class "Default")
      (node (ref "R62") (pin "1") (pinfunction "1_1") (pintype "passive"))
      (node (ref "R74") (pin "1") (pinfunction "1_1") (pintype "passive"))
      (node (ref "U17") (pin "B6") (pinfunction "B6_B6") (pintype "bidirectional"))
    )
    (net (code "15") (name "C1CCSET") (class "Default")
      (node (ref "C31") (pin "1") (pinfunction "1_1") (pintype "passive"))
      (node (ref "R61") (pin "2") (pinfunction "2_2") (pintype "passive"))
      (node (ref "TP10") (pin "1") (pinfunction "1_1") (pintype "bidirectional"))
      (node (ref "U13") (pin "3") (pinfunction "VIN+_3") (pintype "bidirectional"))
    )
    (net (code "16") (name "C1DFB") (class "Default")
      (node (ref "Q7") (pin "3") (pinfunction "S_3") (pintype "bidirectional"))
      (node (ref "R2") (pin "1") (pinfunction "1_1") (pintype "passive"))
      (node (ref "R63") (pin "1") (pinfunction "1_1") (pintype "passive"))
    )
    (net (code "17") (name "C1DOFF") (class "Default")
      (node (ref "D11") (pin "A") (pinfunction "ANODE_A") (pintype "passive"))
      (node (ref "R78") (pin "2") (pinfunction "2_2") (pintype "passive"))
      (node (ref "U17") (pin "B15") (pinfunction "B15_B15") (pintype "bidirectional"))
    )
    (net (code "18") (name "C1NFET") (class "Default")
      (node (ref "R4") (pin "1") (pinfunction "1_1") (pintype "passive"))
      (node (ref "R42") (pin "1") (pinfunction "1_1") (pintype "passive"))
      (node (ref "U7") (pin "3") (pinfunction "IN_3") (pintype "bidirectional"))
    )
    (net (code "19") (name "C1NGATE") (class "Default")
      (node (ref "C15") (pin "2") (pinfunction "2_2") (pintype "passive"))
      (node (ref "R43") (pin "2") (pinfunction "2_2") (pintype "passive"))
      (node (ref "R50") (pin "1") (pinfunction "1_1") (pintype "passive"))
      (node (ref "U13") (pin "1") (pinfunction "VOUT_1") (pintype "bidirectional"))
    )
    (net (code "20") (name "C1ON") (class "Default")
      (node (ref "D7") (pin "A") (pinfunction "ANODE_A") (pintype "passive"))
      (node (ref "R72") (pin "1") (pinfunction "1_1") (pintype "passive"))
      (node (ref "U17") (pin "B14") (pinfunction "B14_B14") (pintype "bidirectional"))
    )
    (net (code "21") (name "C1PFET") (class "Default")
      (node (ref "R45") (pin "1") (pinfunction "1_1") (pintype "passive"))
      (node (ref "R6") (pin "1") (pinfunction "1_1") (pintype "passive"))
      (node (ref "U3") (pin "3") (pinfunction "IN_3") (pintype "bidirectional"))
    )
    (net (code "22") (name "C1R") (class "Default")
      (node (ref "R37") (pin "1") (pinfunction "1_1") (pintype "passive"))
      (node (ref "R39") (pin "2") (pinfunction "2_2") (pintype "passive"))
      (node (ref "U17") (pin "A1") (pinfunction "A1_A1") (pintype "bidirectional"))
    )
    (net (code "23") (name "C1TH") (class "Default")
      (node (ref "C39") (pin "1") (pinfunction "1_1") (pintype "passive"))
      (node (ref "R7") (pin "1") (pinfunction "1_1") (pintype "passive"))
      (node (ref "R8") (pin "1") (pinfunction "1_1") (pintype "passive"))
      (node (ref "U17") (pin "A3") (pinfunction "A3_A3") (pintype "bidirectional"))
    )
    (net (code "24") (name "C1V") (class "Default")
      (node (ref "R21") (pin "2") (pinfunction "2_2") (pintype "passive"))
      (node (ref "U17") (pin "B0") (pinfunction "B0_B0") (pintype "bidirectional"))
      (node (ref "U4") (pin "4") (pinfunction "VOUT_4") (pintype "bidirectional"))
    )
    (net (code "25") (name "C2+") (class "Default")
      (node (ref "BAT3") (pin "1+") (pinfunction "C1+_1+") (pintype "bidirectional"))
      (node (ref "R17") (pin "1") (pinfunction "1_1") (pintype "passive"))
      (node (ref "R86") (pin "2") (pinfunction "2_2") (pintype "passive"))
      (node (ref "U8") (pin "4") (pinfunction "IN+_4") (pintype "bidirectional"))
    )
    (net (code "26") (name "C2-") (class "Default")
      (node (ref "BAT3") (pin "1-") (pinfunction "C1-_1-") (pintype "bidirectional"))
      (node (ref "F2") (pin "2") (pinfunction "2_2") (pintype "bidirectional"))
      (node (ref "R38") (pin "2") (pinfunction "2_2") (pintype "passive"))
      (node (ref "R84") (pin "2") (pinfunction "2_2") (pintype "passive"))
    )
    (net (code "27") (name "C2A") (class "Default")
      (node (ref "R24") (pin "2") (pinfunction "2_2") (pintype "passive"))
      (node (ref "TP8") (pin "1") (pinfunction "1_1") (pintype "bidirectional"))
      (node (ref "U17") (pin "A7") (pinfunction "A7_A7") (pintype "bidirectional"))
    )
    (net (code "28") (name "C2CCPWM") (class "Default")
      (node (ref "R69") (pin "1") (pinfunction "1_1") (pintype "passive"))
      (node (ref "R75") (pin "1") (pinfunction "1_1") (pintype "passive"))
      (node (ref "U17") (pin "B7") (pinfunction "B7_B7") (pintype "bidirectional"))
    )
    (net (code "29") (name "C2CCSET") (class "Default")
      (node (ref "C34") (pin "1") (pinfunction "1_1") (pintype "passive"))
      (node (ref "R66") (pin "2") (pinfunction "2_2") (pintype "passive"))
      (node (ref "TP11") (pin "1") (pinfunction "1_1") (pintype "bidirectional"))
      (node (ref "U14") (pin "3") (pinfunction "VIN+_3") (pintype "bidirectional"))
    )
    (net (code "30") (name "C2DFB") (class "Default")
      (node (ref "Q8") (pin "3") (pinfunction "S_3") (pintype "bidirectional"))
      (node (ref "R3") (pin "1") (pinfunction "1_1") (pintype "passive"))
      (node (ref "R67") (pin "1") (pinfunction "1_1") (pintype "passive"))
    )
    (net (code "31") (name "C2DOFF") (class "Default")
      (node (ref "D12") (pin "A") (pinfunction "ANODE_A") (pintype "passive"))
      (node (ref "R79") (pin "2") (pinfunction "2_2") (pintype "passive"))
      (node (ref "U17") (pin "A15") (pinfunction "A15_A15") (pintype "bidirectional"))
    )
    (net (code "32") (name "C2NFET") (class "Default")
      (node (ref "R30") (pin "1") (pinfunction "1_1") (pintype "passive"))
      (node (ref "R46") (pin "1") (pinfunction "1_1") (pintype "passive"))
      (node (ref "U11") (pin "3") (pinfunction "IN_3") (pintype "bidirectional"))
    )
    (net (code "33") (name "C2NGATE") (class "Default")
      (node (ref "C33") (pin "2") (pinfunction "2_2") (pintype "passive"))
      (node (ref "R44") (pin "2") (pinfunction "2_2") (pintype "passive"))
      (node (ref "R51") (pin "1") (pinfunction "1_1") (pintype "passive"))
      (node (ref "U14") (pin "1") (pinfunction "VOUT_1") (pintype "bidirectional"))
    )
    (net (code "34") (name "C2ON") (class "Default")
      (node (ref "D8") (pin "A") (pinfunction "ANODE_A") (pintype "passive"))
      (node (ref "R73") (pin "1") (pinfunction "1_1") (pintype "passive"))
      (node (ref "U17") (pin "B3") (pinfunction "B3_B3") (pintype "bidirectional"))
    )
    (net (code "35") (name "C2PFET") (class "Default")
      (node (ref "R47") (pin "1") (pinfunction "1_1") (pintype "passive"))
      (node (ref "R57") (pin "1") (pinfunction "1_1") (pintype "passive"))
      (node (ref "U10") (pin "3") (pinfunction "IN_3") (pintype "bidirectional"))
    )
    (net (code "36") (name "C2R") (class "Default")
      (node (ref "R38") (pin "1") (pinfunction "1_1") (pintype "passive"))
      (node (ref "R40") (pin "2") (pinfunction "2_2") (pintype "passive"))
      (node (ref "U17") (pin "A0") (pinfunction "A0_A0") (pintype "bidirectional"))
    )
    (net (code "37") (name "C2TH") (class "Default")
      (node (ref "C40") (pin "1") (pinfunction "1_1") (pintype "passive"))
      (node (ref "R31") (pin "1") (pinfunction "1_1") (pintype "passive"))
      (node (ref "R32") (pin "1") (pinfunction "1_1") (pintype "passive"))
      (node (ref "U17") (pin "A2") (pinfunction "A2_A2") (pintype "bidirectional"))
    )
    (net (code "38") (name "C2V") (class "Default")
      (node (ref "R29") (pin "2") (pinfunction "2_2") (pintype "passive"))
      (node (ref "U17") (pin "A6") (pinfunction "A6_A6") (pintype "bidirectional"))
      (node (ref "U9") (pin "4") (pinfunction "VOUT_4") (pintype "bidirectional"))
    )
    (net (code "39") (name "DI") (class "Default")
      (node (ref "Q16") (pin "1") (pinfunction "G_1") (pintype "bidirectional"))
      (node (ref "U17") (pin "B13") (pinfunction "B13_B13") (pintype "bidirectional"))
    )
    (net (code "40") (name "DI2") (class "Default")
      (node (ref "LED7") (pin "2-DOUT") (pinfunction "DOUT_2-DOUT") (pintype "output"))
      (node (ref "LED8") (pin "4-DIN") (pinfunction "DIN_4-DIN") (pintype "input"))
    )
    (net (code "41") (name "FANON") (class "Default")
      (node (ref "Q9") (pin "1") (pinfunction "G_1") (pintype "bidirectional"))
      (node (ref "U17") (pin "B4") (pinfunction "B4_B4") (pintype "bidirectional"))
    )
    (net (code "42") (name "GND") (class "Default")
      (node (ref "C1") (pin "2") (pinfunction "2_2") (pintype "passive"))
      (node (ref "C10") (pin "-") (pinfunction "-_-") (pintype "passive"))
      (node (ref "C11") (pin "2") (pinfunction "2_2") (pintype "passive"))
      (node (ref "C12") (pin "2") (pinfunction "2_2") (pintype "passive"))
      (node (ref "C13") (pin "2") (pinfunction "2_2") (pintype "passive"))
      (node (ref "C14") (pin "2") (pinfunction "2_2") (pintype "passive"))
      (node (ref "C16") (pin "2") (pinfunction "2_2") (pintype "passive"))
      (node (ref "C17") (pin "2") (pinfunction "2_2") (pintype "passive"))
      (node (ref "C18") (pin "2") (pinfunction "2_2") (pintype "passive"))
      (node (ref "C19") (pin "2") (pinfunction "2_2") (pintype "passive"))
      (node (ref "C2") (pin "2") (pinfunction "2_2") (pintype "passive"))
      (node (ref "C20") (pin "2") (pinfunction "2_2") (pintype "passive"))
      (node (ref "C21") (pin "-") (pinfunction "-_-") (pintype "passive"))
      (node (ref "C22") (pin "-") (pinfunction "-_-") (pintype "passive"))
      (node (ref "C23") (pin "2") (pinfunction "2_2") (pintype "passive"))
      (node (ref "C24") (pin "2") (pinfunction "2_2") (pintype "passive"))
      (node (ref "C25") (pin "2") (pinfunction "2_2") (pintype "passive"))
      (node (ref "C26") (pin "-") (pinfunction "-_-") (pintype "passive"))
      (node (ref "C27") (pin "2") (pinfunction "2_2") (pintype "passive"))
      (node (ref "C28") (pin "2") (pinfunction "2_2") (pintype "passive"))
      (node (ref "C29") (pin "2") (pinfunction "2_2") (pintype "passive"))
      (node (ref "C3") (pin "2") (pinfunction "2_2") (pintype "passive"))
      (node (ref "C30") (pin "2") (pinfunction "2_2") (pintype "passive"))
      (node (ref "C31") (pin "2") (pinfunction "2_2") (pintype "passive"))
      (node (ref "C32") (pin "2") (pinfunction "2_2") (pintype "passive"))
      (node (ref "C34") (pin "2") (pinfunction "2_2") (pintype "passive"))
      (node (ref "C35") (pin "2") (pinfunction "2_2") (pintype "passive"))
      (node (ref "C36") (pin "2") (pinfunction "2_2") (pintype "passive"))
      (node (ref "C37") (pin "2") (pinfunction "2_2") (pintype "passive"))
      (node (ref "C38") (pin "2") (pinfunction "2_2") (pintype "passive"))
      (node (ref "C39") (pin "2") (pinfunction "2_2") (pintype "passive"))
      (node (ref "C4") (pin "2") (pinfunction "2_2") (pintype "passive"))
      (node (ref "C40") (pin "2") (pinfunction "2_2") (pintype "passive"))
      (node (ref "C41") (pin "2") (pinfunction "2_2") (pintype "passive"))
      (node (ref "C42") (pin "2") (pinfunction "2_2") (pintype "passive"))
      (node (ref "C43") (pin "2") (pinfunction "2_2") (pintype "passive"))
      (node (ref "C5") (pin "2") (pinfunction "2_2") (pintype "passive"))
      (node (ref "C6") (pin "2") (pinfunction "2_2") (pintype "passive"))
      (node (ref "C7") (pin "-") (pinfunction "-_-") (pintype "passive"))
      (node (ref "C8") (pin "-") (pinfunction "-_-") (pintype "passive"))
      (node (ref "C9") (pin "2") (pinfunction "2_2") (pintype "passive"))
      (node (ref "D1") (pin "A") (pinfunction "ANODE_A") (pintype "passive"))
      (node (ref "D13") (pin "A") (pinfunction "ANODE_A") (pintype "passive"))
      (node (ref "D14") (pin "A") (pinfunction "ANODE_A") (pintype "passive"))
      (node (ref "D16") (pin "A") (pinfunction "ANODE_A") (pintype "passive"))
      (node (ref "D17") (pin "A") (pinfunction "ANODE_A") (pintype "passive"))
      (node (ref "D3") (pin "A") (pinfunction "ANODE_A") (pintype "passive"))
      (node (ref "D9") (pin "A") (pinfunction "ANODE_A") (pintype "passive"))
      (node (ref "J1") (pin "1") (pinfunction "1_1") (pintype "passive"))
      (node (ref "JP1") (pin "1") (pinfunction "1_1") (pintype "passive"))
      (node (ref "JP2") (pin "3") (pinfunction "3_3") (pintype "passive"))
      (node (ref "JP3") (pin "3") (pinfunction "3_3") (pintype "passive"))
      (node (ref "JP4") (pin "3") (pinfunction "3_3") (pintype "passive"))
      (node (ref "JP5") (pin "3") (pinfunction "3_3") (pintype "passive"))
      (node (ref "LCD1") (pin "1=GND") (pinfunction "GND_1=GND") (pintype "bidirectional"))
      (node (ref "LED6") (pin "C") (pinfunction "C_C") (pintype "passive"))
      (node (ref "LED7") (pin "3-GND") (pinfunction "GND_3-GND") (pintype "bidirectional"))
      (node (ref "LED8") (pin "3-GND") (pinfunction "GND_3-GND") (pintype "bidirectional"))
      (node (ref "Q1") (pin "2") (pinfunction "S_2") (pintype "passive"))
      (node (ref "Q10") (pin "1") (pinfunction "S_1") (pintype "bidirectional"))
      (node (ref "Q10") (pin "2") (pinfunction "S_2") (pintype "bidirectional"))
      (node (ref "Q10") (pin "3") (pinfunction "S_3") (pintype "bidirectional"))
      (node (ref "Q11") (pin "1") (pinfunction "S_1") (pintype "bidirectional"))
      (node (ref "Q11") (pin "2") (pinfunction "S_2") (pintype "bidirectional"))
      (node (ref "Q11") (pin "3") (pinfunction "S_3") (pintype "bidirectional"))
      (node (ref "Q12") (pin "1") (pinfunction "S_1") (pintype "bidirectional"))
      (node (ref "Q12") (pin "2") (pinfunction "S_2") (pintype "bidirectional"))
      (node (ref "Q12") (pin "3") (pinfunction "S_3") (pintype "bidirectional"))
      (node (ref "Q13") (pin "1") (pinfunction "S_1") (pintype "bidirectional"))
      (node (ref "Q13") (pin "2") (pinfunction "S_2") (pintype "bidirectional"))
      (node (ref "Q13") (pin "3") (pinfunction "S_3") (pintype "bidirectional"))
      (node (ref "Q16") (pin "2") (pinfunction "S_2") (pintype "bidirectional"))
      (node (ref "Q3") (pin "2") (pinfunction "S_2") (pintype "passive"))
      (node (ref "Q4") (pin "2") (pinfunction "S_2") (pintype "passive"))
      (node (ref "Q6") (pin "2") (pinfunction "S_2") (pintype "passive"))
      (node (ref "Q9") (pin "2") (pinfunction "S_2") (pintype "bidirectional"))
      (node (ref "R11") (pin "2") (pinfunction "2_2") (pintype "passive"))
      (node (ref "R13") (pin "1") (pinfunction "1_1") (pintype "passive"))
      (node (ref "R19") (pin "1") (pinfunction "1_1") (pintype "passive"))
      (node (ref "R2") (pin "2") (pinfunction "2_2") (pintype "passive"))
      (node (ref "R23") (pin "1") (pinfunction "1_1") (pintype "passive"))
      (node (ref "R27") (pin "1") (pinfunction "1_1") (pintype "passive"))
      (node (ref "R3") (pin "2") (pinfunction "2_2") (pintype "passive"))
      (node (ref "R32") (pin "2") (pinfunction "2_2") (pintype "passive"))
      (node (ref "R36") (pin "1") (pinfunction "1_1") (pintype "passive"))
      (node (ref "R39") (pin "1") (pinfunction "1_1") (pintype "passive"))
      (node (ref "R40") (pin "1") (pinfunction "1_1") (pintype "passive"))
      (node (ref "R49") (pin "2") (pinfunction "2_2") (pintype "passive"))
      (node (ref "R50") (pin "2") (pinfunction "2_2") (pintype "passive"))
      (node (ref "R51") (pin "2") (pinfunction "2_2") (pintype "passive"))
      (node (ref "R52") (pin "1") (pinfunction "1_1") (pintype "passive"))
      (node (ref "R56") (pin "2") (pinfunction "2_2") (pintype "passive"))
      (node (ref "R60") (pin "2") (pinfunction "2_2") (pintype "passive"))
      (node (ref "R65") (pin "1") (pinfunction "1_1") (pintype "passive"))
      (node (ref "R70") (pin "1") (pinfunction "1_1") (pintype "passive"))
      (node (ref "R72") (pin "2") (pinfunction "2_2") (pintype "passive"))
      (node (ref "R73") (pin "2") (pinfunction "2_2") (pintype "passive"))
      (node (ref "R74") (pin "2") (pinfunction "2_2") (pintype "passive"))
      (node (ref "R75") (pin "2") (pinfunction "2_2") (pintype "passive"))
      (node (ref "R76") (pin "2") (pinfunction "2_2") (pintype "passive"))
      (node (ref "R8") (pin "2") (pinfunction "2_2") (pintype "passive"))
      (node (ref "R80") (pin "2") (pinfunction "2_2") (pintype "passive"))
      (node (ref "R81") (pin "2") (pinfunction "2_2") (pintype "passive"))
      (node (ref "R89") (pin "1") (pinfunction "1_1") (pintype "passive"))
      (node (ref "S1") (pin "3") (pinfunction "3_3") (pintype "passive"))
      (node (ref "S1") (pin "4") (pinfunction "4_4") (pintype "passive"))
      (node (ref "S2") (pin "3") (pinfunction "3_3") (pintype "passive"))
      (node (ref "S2") (pin "4") (pinfunction "4_4") (pintype "passive"))
      (node (ref "T1") (pin "1") (pinfunction "1_1") (pintype "bidirectional"))
      (node (ref "T2") (pin "1") (pinfunction "1_1") (pintype "bidirectional"))
      (node (ref "U1") (pin "2") (pinfunction "GND_2") (pintype "bidirectional"))
      (node (ref "U10") (pin "1") (pinfunction "GND_1") (pintype "bidirectional"))
      (node (ref "U10") (pin "4") (pinfunction "GND_4") (pintype "bidirectional"))
      (node (ref "U11") (pin "1") (pinfunction "GND_1") (pintype "bidirectional"))
      (node (ref "U11") (pin "4") (pinfunction "GND_4") (pintype "bidirectional"))
      (node (ref "U12") (pin "4") (pinfunction "GND_4") (pintype "bidirectional"))
      (node (ref "U13") (pin "2") (pinfunction "VSS_2") (pintype "bidirectional"))
      (node (ref "U14") (pin "2") (pinfunction "VSS_2") (pintype "bidirectional"))
      (node (ref "U15") (pin "2") (pinfunction "GND_2") (pintype "bidirectional"))
      (node (ref "U16") (pin "2") (pinfunction "GND_2") (pintype "bidirectional"))
      (node (ref "U16") (pin "2@1") (pinfunction "GND_2@1") (pintype "bidirectional"))
      (node (ref "U17") (pin "GND") (pinfunction "GND_GND") (pintype "bidirectional"))
      (node (ref "U17") (pin "GND2") (pinfunction "GND2_GND2") (pintype "bidirectional"))
      (node (ref "U17") (pin "GND3") (pinfunction "GND3_GND3") (pintype "bidirectional"))
      (node (ref "U17") (pin "GND4") (pinfunction "GND4_GND4") (pintype "bidirectional"))
      (node (ref "U17") (pin "GND5") (pinfunction "GND5_GND5") (pintype "bidirectional"))
      (node (ref "U18") (pin "2") (pinfunction "GND_2") (pintype "bidirectional"))
      (node (ref "U2") (pin "1") (pinfunction "GND_1") (pintype "bidirectional"))
      (node (ref "U3") (pin "1") (pinfunction "GND_1") (pintype "bidirectional"))
      (node (ref "U3") (pin "4") (pinfunction "GND_4") (pintype "bidirectional"))
      (node (ref "U4") (pin "2") (pinfunction "VSS_2") (pintype "bidirectional"))
      (node (ref "U5") (pin "2") (pinfunction "A_2") (pintype "passive"))
      (node (ref "U5") (pin "5") (pinfunction "A_5") (pintype "passive"))
      (node (ref "U6") (pin "3") (pinfunction "A_3") (pintype "passive"))
      (node (ref "U7") (pin "1") (pinfunction "GND_1") (pintype "bidirectional"))
      (node (ref "U7") (pin "4") (pinfunction "GND_4") (pintype "bidirectional"))
      (node (ref "U8") (pin "2") (pinfunction "GND_2") (pintype "bidirectional"))
      (node (ref "U9") (pin "2") (pinfunction "VSS_2") (pintype "bidirectional"))
    )
    (net (code "43") (name "HSTH") (class "Default")
      (node (ref "C41") (pin "1") (pinfunction "1_1") (pintype "passive"))
      (node (ref "R77") (pin "1") (pinfunction "1_1") (pintype "passive"))
      (node (ref "T1") (pin "2") (pinfunction "2_2") (pintype "bidirectional"))
      (node (ref "U18") (pin "1") (pinfunction "2_1") (pintype "bidirectional"))
    )
    (net (code "44") (name "HSTH2") (class "Default")
      (node (ref "C43") (pin "1") (pinfunction "1_1") (pintype "passive"))
      (node (ref "R14") (pin "1") (pinfunction "1_1") (pintype "passive"))
      (node (ref "T2") (pin "2") (pinfunction "2_2") (pintype "bidirectional"))
      (node (ref "U15") (pin "3") (pinfunction "1_3") (pintype "bidirectional"))
    )
    (net (code "45") (name "ISNS_REF") (class "Default")
      (node (ref "C11") (pin "1") (pinfunction "1_1") (pintype "passive"))
      (node (ref "C16") (pin "1") (pinfunction "1_1") (pintype "passive"))
      (node (ref "C28") (pin "1") (pinfunction "1_1") (pintype "passive"))
      (node (ref "R10") (pin "2") (pinfunction "2_2") (pintype "passive"))
      (node (ref "R11") (pin "1") (pinfunction "1_1") (pintype "passive"))
      (node (ref "TP5") (pin "1") (pinfunction "1_1") (pintype "bidirectional"))
      (node (ref "TP7") (pin "1") (pinfunction "1_1") (pintype "bidirectional"))
      (node (ref "U1") (pin "1") (pinfunction "REF_1") (pintype "bidirectional"))
      (node (ref "U17") (pin "A5") (pinfunction "A5_A5") (pintype "bidirectional"))
      (node (ref "U8") (pin "1") (pinfunction "REF_1") (pintype "bidirectional"))
    )
    (net (code "46") (name "Net-(C15-Pad1)") (class "Default")
      (node (ref "C15") (pin "1") (pinfunction "1_1") (pintype "passive"))
      (node (ref "R64") (pin "2") (pinfunction "2_2") (pintype "passive"))
    )
    (net (code "47") (name "Net-(C33-Pad1)") (class "Default")
      (node (ref "C33") (pin "1") (pinfunction "1_1") (pintype "passive"))
      (node (ref "R68") (pin "2") (pinfunction "2_2") (pintype "passive"))
    )
    (net (code "48") (name "Net-(D1-CATHODE)") (class "Default")
      (node (ref "D1") (pin "K") (pinfunction "CATHODE_K") (pintype "passive"))
      (node (ref "D13") (pin "K") (pinfunction "CATHODE_K") (pintype "passive"))
      (node (ref "D16") (pin "K") (pinfunction "CATHODE_K") (pintype "passive"))
      (node (ref "F3") (pin "1") (pinfunction "1_1") (pintype "bidirectional"))
      (node (ref "L1") (pin "1") (pinfunction "P$1_1") (pintype "passive"))
      (node (ref "L3") (pin "P$1") (pinfunction "P$1_P$1") (pintype "passive"))
      (node (ref "Q10") (pin "5") (pinfunction "D_5") (pintype "bidirectional"))
      (node (ref "Q10") (pin "6") (pinfunction "D_6") (pintype "bidirectional"))
      (node (ref "Q10") (pin "7") (pinfunction "D_7") (pintype "bidirectional"))
      (node (ref "Q10") (pin "8") (pinfunction "D_8") (pintype "bidirectional"))
      (node (ref "Q3") (pin "3") (pinfunction "D_3") (pintype "passive"))
    )
    (net (code "49") (name "Net-(D5-CATHODE)") (class "Default")
      (node (ref "D5") (pin "K") (pinfunction "CATHODE_K") (pintype "passive"))
      (node (ref "D7") (pin "K") (pinfunction "CATHODE_K") (pintype "passive"))
      (node (ref "Q1") (pin "1") (pinfunction "G_1") (pintype "input"))
      (node (ref "Q11") (pin "4") (pinfunction "G_4") (pintype "bidirectional"))
      (node (ref "R23") (pin "2") (pinfunction "2_2") (pintype "passive"))
    )
    (net (code "50") (name "Net-(D6-CATHODE)") (class "Default")
      (node (ref "D6") (pin "K") (pinfunction "CATHODE_K") (pintype "passive"))
      (node (ref "D8") (pin "K") (pinfunction "CATHODE_K") (pintype "passive"))
      (node (ref "Q12") (pin "4") (pinfunction "G_4") (pintype "bidirectional"))
      (node (ref "Q6") (pin "1") (pinfunction "G_1") (pintype "input"))
      (node (ref "R36") (pin "2") (pinfunction "2_2") (pintype "passive"))
    )
    (net (code "51") (name "Net-(D10-ANODE)") (class "Default")
      (node (ref "D10") (pin "A") (pinfunction "ANODE_A") (pintype "passive"))
      (node (ref "D18") (pin "A") (pinfunction "ANODE_A") (pintype "passive"))
      (node (ref "D2") (pin "A") (pinfunction "ANODE_A") (pintype "passive"))
      (node (ref "F3") (pin "2") (pinfunction "2_2") (pintype "bidirectional"))
      (node (ref "Q14") (pin "5") (pinfunction "D_5") (pintype "bidirectional"))
      (node (ref "Q14") (pin "6") (pinfunction "D_6") (pintype "bidirectional"))
      (node (ref "Q14") (pin "7") (pinfunction "D_7") (pintype "bidirectional"))
      (node (ref "Q14") (pin "8") (pinfunction "D_8") (pintype "bidirectional"))
      (node (ref "Q2") (pin "3") (pinfunction "D_3") (pintype "bidirectional"))
    )
    (net (code "52") (name "Net-(D11-CATHODE)") (class "Default")
      (node (ref "D11") (pin "K") (pinfunction "CATHODE_K") (pintype "passive"))
      (node (ref "R63") (pin "2") (pinfunction "2_2") (pintype "passive"))
      (node (ref "R64") (pin "1") (pinfunction "1_1") (pintype "passive"))
      (node (ref "U13") (pin "4") (pinfunction "VIN-_4") (pintype "bidirectional"))
    )
    (net (code "53") (name "Net-(D12-CATHODE)") (class "Default")
      (node (ref "D12") (pin "K") (pinfunction "CATHODE_K") (pintype "passive"))
      (node (ref "R67") (pin "2") (pinfunction "2_2") (pintype "passive"))
      (node (ref "R68") (pin "1") (pinfunction "1_1") (pintype "passive"))
      (node (ref "U14") (pin "4") (pinfunction "VIN-_4") (pintype "bidirectional"))
    )
    (net (code "54") (name "Net-(D14-CATHODE)") (class "Default")
      (node (ref "D14") (pin "K") (pinfunction "CATHODE_K") (pintype "passive"))
      (node (ref "D17") (pin "K") (pinfunction "CATHODE_K") (pintype "passive"))
      (node (ref "D3") (pin "K") (pinfunction "CATHODE_K") (pintype "passive"))
      (node (ref "F4") (pin "1") (pinfunction "1_1") (pintype "bidirectional"))
      (node (ref "L2") (pin "1") (pinfunction "P$1_1") (pintype "passive"))
      (node (ref "L4") (pin "P$1") (pinfunction "P$1_P$1") (pintype "passive"))
      (node (ref "Q13") (pin "5") (pinfunction "D_5") (pintype "bidirectional"))
      (node (ref "Q13") (pin "6") (pinfunction "D_6") (pintype "bidirectional"))
      (node (ref "Q13") (pin "7") (pinfunction "D_7") (pintype "bidirectional"))
      (node (ref "Q13") (pin "8") (pinfunction "D_8") (pintype "bidirectional"))
      (node (ref "Q4") (pin "3") (pinfunction "D_3") (pintype "passive"))
    )
    (net (code "55") (name "Net-(D15-ANODE)") (class "Default")
      (node (ref "D15") (pin "A") (pinfunction "ANODE_A") (pintype "passive"))
      (node (ref "D19") (pin "A") (pinfunction "ANODE_A") (pintype "passive"))
      (node (ref "D4") (pin "A") (pinfunction "ANODE_A") (pintype "passive"))
      (node (ref "F4") (pin "2") (pinfunction "2_2") (pintype "bidirectional"))
      (node (ref "Q15") (pin "5") (pinfunction "D_5") (pintype "bidirectional"))
      (node (ref "Q15") (pin "6") (pinfunction "D_6") (pintype "bidirectional"))
      (node (ref "Q15") (pin "7") (pinfunction "D_7") (pintype "bidirectional"))
      (node (ref "Q15") (pin "8") (pinfunction "D_8") (pintype "bidirectional"))
      (node (ref "Q5") (pin "3") (pinfunction "D_3") (pintype "bidirectional"))
    )
    (net (code "56") (name "Net-(J1-Pad2)") (class "Default")
      (node (ref "J1") (pin "2") (pinfunction "2_2") (pintype "passive"))
      (node (ref "R22") (pin "1") (pinfunction "1_1") (pintype "passive"))
    )
    (net (code "57") (name "Net-(L1-P$2)") (class "Default")
      (node (ref "C26") (pin "+") (pinfunction "+_+") (pintype "passive"))
      (node (ref "C5") (pin "1") (pinfunction "1_1") (pintype "passive"))
      (node (ref "C8") (pin "+") (pinfunction "+_+") (pintype "passive"))
      (node (ref "L1") (pin "2") (pinfunction "P$2_2") (pintype "passive"))
      (node (ref "L3") (pin "P$2") (pinfunction "P$2_P$2") (pintype "passive"))
      (node (ref "Q7") (pin "2") (pinfunction "D_2") (pintype "bidirectional"))
      (node (ref "R1") (pin "2") (pinfunction "2_2") (pintype "passive"))
      (node (ref "U1") (pin "5") (pinfunction "IN-_5") (pintype "bidirectional"))
    )
    (net (code "58") (name "Net-(L2-P$2)") (class "Default")
      (node (ref "C20") (pin "1") (pinfunction "1_1") (pintype "passive"))
      (node (ref "C21") (pin "+") (pinfunction "+_+") (pintype "passive"))
      (node (ref "C22") (pin "+") (pinfunction "+_+") (pintype "passive"))
      (node (ref "L2") (pin "2") (pinfunction "P$2_2") (pintype "passive"))
      (node (ref "L4") (pin "P$2") (pinfunction "P$2_P$2") (pintype "passive"))
      (node (ref "Q8") (pin "2") (pinfunction "D_2") (pintype "bidirectional"))
      (node (ref "R17") (pin "2") (pinfunction "2_2") (pintype "passive"))
      (node (ref "U8") (pin "5") (pinfunction "IN-_5") (pintype "bidirectional"))
    )
    (net (code "59") (name "Net-(LED3-PadC)") (class "Default")
      (node (ref "LED3") (pin "C") (pinfunction "C_C") (pintype "passive"))
      (node (ref "R88") (pin "2") (pinfunction "2_2") (pintype "passive"))
    )
    (net (code "60") (name "Net-(LED4-PadC)") (class "Default")
      (node (ref "LED4") (pin "C") (pinfunction "C_C") (pintype "passive"))
      (node (ref "R52") (pin "2") (pinfunction "2_2") (pintype "passive"))
    )
    (net (code "61") (name "Net-(LED5-PadC)") (class "Default")
      (node (ref "LED5") (pin "C") (pinfunction "C_C") (pintype "passive"))
      (node (ref "R89") (pin "2") (pinfunction "2_2") (pintype "passive"))
    )
    (net (code "62") (name "Net-(LED6-PadA)") (class "Default")
      (node (ref "LED6") (pin "A") (pinfunction "A_A") (pintype "passive"))
      (node (ref "R90") (pin "2") (pinfunction "2_2") (pintype "passive"))
    )
    (net (code "63") (name "Net-(LED7-DIN)") (class "Default")
      (node (ref "LED7") (pin "4-DIN") (pinfunction "DIN_4-DIN") (pintype "input"))
      (node (ref "Q16") (pin "3") (pinfunction "D_3") (pintype "bidirectional"))
      (node (ref "R41") (pin "2") (pinfunction "2_2") (pintype "passive"))
    )
    (net (code "64") (name "Net-(LED8-DOUT)") (class "Default")
      (node (ref "JP8") (pin "1") (pinfunction "1_1") (pintype "passive"))
      (node (ref "LED8") (pin "2-DOUT") (pinfunction "DOUT_2-DOUT") (pintype "output"))
    )
    (net (code "65") (name "Net-(Q1-D)") (class "Default")
      (node (ref "F1") (pin "1") (pinfunction "1_1") (pintype "bidirectional"))
      (node (ref "Q1") (pin "3") (pinfunction "D_3") (pintype "passive"))
      (node (ref "Q11") (pin "5") (pinfunction "D_5") (pintype "bidirectional"))
      (node (ref "Q11") (pin "6") (pinfunction "D_6") (pintype "bidirectional"))
      (node (ref "Q11") (pin "7") (pinfunction "D_7") (pintype "bidirectional"))
      (node (ref "Q11") (pin "8") (pinfunction "D_8") (pintype "bidirectional"))
    )
    (net (code "66") (name "Net-(Q6-D)") (class "Default")
      (node (ref "F2") (pin "1") (pinfunction "1_1") (pintype "bidirectional"))
      (node (ref "Q12") (pin "5") (pinfunction "D_5") (pintype "bidirectional"))
      (node (ref "Q12") (pin "6") (pinfunction "D_6") (pintype "bidirectional"))
      (node (ref "Q12") (pin "7") (pinfunction "D_7") (pintype "bidirectional"))
      (node (ref "Q12") (pin "8") (pinfunction "D_8") (pintype "bidirectional"))
      (node (ref "Q6") (pin "3") (pinfunction "D_3") (pintype "passive"))
    )
    (net (code "67") (name "Net-(Q7-G)") (class "Default")
      (node (ref "Q7") (pin "1") (pinfunction "G_1") (pintype "bidirectional"))
      (node (ref "R43") (pin "1") (pinfunction "1_1") (pintype "passive"))
    )
    (net (code "68") (name "Net-(Q8-G)") (class "Default")
      (node (ref "Q8") (pin "1") (pinfunction "G_1") (pintype "bidirectional"))
      (node (ref "R44") (pin "1") (pinfunction "1_1") (pintype "passive"))
    )
    (net (code "69") (name "Net-(Q9-D)") (class "Default")
      (node (ref "J2") (pin "2") (pinfunction "2_2") (pintype "passive"))
      (node (ref "Q9") (pin "3") (pinfunction "D_3") (pintype "bidirectional"))
    )
    (net (code "70") (name "Net-(Q10-G)") (class "Default")
      (node (ref "LED4") (pin "A") (pinfunction "A_A") (pintype "passive"))
      (node (ref "Q10") (pin "4") (pinfunction "G_4") (pintype "bidirectional"))
      (node (ref "Q3") (pin "1") (pinfunction "G_1") (pintype "input"))
      (node (ref "R4") (pin "2") (pinfunction "2_2") (pintype "passive"))
      (node (ref "R56") (pin "1") (pinfunction "1_1") (pintype "passive"))
      (node (ref "U7") (pin "5") (pinfunction "OUT/N_5") (pintype "bidirectional"))
    )
    (net (code "71") (name "Net-(Q13-G)") (class "Default")
      (node (ref "LED5") (pin "A") (pinfunction "A_A") (pintype "passive"))
      (node (ref "Q13") (pin "4") (pinfunction "G_4") (pintype "bidirectional"))
      (node (ref "Q4") (pin "1") (pinfunction "G_1") (pintype "input"))
      (node (ref "R30") (pin "2") (pinfunction "2_2") (pintype "passive"))
      (node (ref "R60") (pin "1") (pinfunction "1_1") (pintype "passive"))
      (node (ref "U11") (pin "5") (pinfunction "OUT/N_5") (pintype "bidirectional"))
    )
    (net (code "72") (name "Net-(Q14-G)") (class "Default")
      (node (ref "Q14") (pin "4") (pinfunction "G_4") (pintype "bidirectional"))
      (node (ref "Q2") (pin "1") (pinfunction "G_1") (pintype "bidirectional"))
      (node (ref "R5") (pin "2") (pinfunction "2_2") (pintype "passive"))
      (node (ref "R88") (pin "1") (pinfunction "1_1") (pintype "passive"))
      (node (ref "U3") (pin "5") (pinfunction "OUT/N_5") (pintype "bidirectional"))
    )
    (net (code "73") (name "Net-(Q15-G)") (class "Default")
      (node (ref "Q15") (pin "4") (pinfunction "G_4") (pintype "bidirectional"))
      (node (ref "Q5") (pin "1") (pinfunction "G_1") (pintype "bidirectional"))
      (node (ref "R58") (pin "1") (pinfunction "1_1") (pintype "passive"))
      (node (ref "R90") (pin "1") (pinfunction "1_1") (pintype "passive"))
      (node (ref "U10") (pin "5") (pinfunction "OUT/N_5") (pintype "bidirectional"))
    )
    (net (code "74") (name "Net-(R61-Pad1)") (class "Default")
      (node (ref "R61") (pin "1") (pinfunction "1_1") (pintype "passive"))
      (node (ref "R62") (pin "2") (pinfunction "2_2") (pintype "passive"))
      (node (ref "R65") (pin "2") (pinfunction "2_2") (pintype "passive"))
    )
    (net (code "75") (name "Net-(R66-Pad1)") (class "Default")
      (node (ref "R66") (pin "1") (pinfunction "1_1") (pintype "passive"))
      (node (ref "R69") (pin "2") (pinfunction "2_2") (pintype "passive"))
      (node (ref "R70") (pin "2") (pinfunction "2_2") (pintype "passive"))
    )
    (net (code "76") (name "Net-(TP1-1)") (class "Default")
      (node (ref "R55") (pin "2") (pinfunction "2_2") (pintype "passive"))
      (node (ref "TP1") (pin "P$1") (pinfunction "1_P$1") (pintype "bidirectional"))
    )
    (net (code "77") (name "Net-(TP2-1)") (class "Default")
      (node (ref "R83") (pin "2") (pinfunction "2_2") (pintype "passive"))
      (node (ref "TP2") (pin "P$1") (pinfunction "1_P$1") (pintype "bidirectional"))
    )
    (net (code "78") (name "Net-(TP3-1)") (class "Default")
      (node (ref "R85") (pin "2") (pinfunction "2_2") (pintype "passive"))
      (node (ref "TP3") (pin "P$1") (pinfunction "1_P$1") (pintype "bidirectional"))
    )
    (net (code "79") (name "Net-(TP4-1)") (class "Default")
      (node (ref "R87") (pin "2") (pinfunction "2_2") (pintype "passive"))
      (node (ref "TP4") (pin "P$1") (pinfunction "1_P$1") (pintype "bidirectional"))
    )
    (net (code "80") (name "Net-(U1-OUT)") (class "Default")
      (node (ref "R12") (pin "1") (pinfunction "1_1") (pintype "passive"))
      (node (ref "U1") (pin "6") (pinfunction "OUT_6") (pintype "bidirectional"))
    )
    (net (code "81") (name "Net-(U4-VIN+)") (class "Default")
      (node (ref "R18") (pin "2") (pinfunction "2_2") (pintype "passive"))
      (node (ref "R19") (pin "2") (pinfunction "2_2") (pintype "passive"))
      (node (ref "U4") (pin "1") (pinfunction "VIN+_1") (pintype "bidirectional"))
    )
    (net (code "82") (name "Net-(U4-VIN-)") (class "Default")
      (node (ref "R20") (pin "2") (pinfunction "2_2") (pintype "passive"))
      (node (ref "R21") (pin "1") (pinfunction "1_1") (pintype "passive"))
      (node (ref "U4") (pin "3") (pinfunction "VIN-_3") (pintype "bidirectional"))
    )
    (net (code "83") (name "Net-(U8-OUT)") (class "Default")
      (node (ref "R24") (pin "1") (pinfunction "1_1") (pintype "passive"))
      (node (ref "U8") (pin "6") (pinfunction "OUT_6") (pintype "bidirectional"))
    )
    (net (code "84") (name "Net-(U9-VIN+)") (class "Default")
      (node (ref "R26") (pin "2") (pinfunction "2_2") (pintype "passive"))
      (node (ref "R27") (pin "2") (pinfunction "2_2") (pintype "passive"))
      (node (ref "U9") (pin "1") (pinfunction "VIN+_1") (pintype "bidirectional"))
    )
    (net (code "85") (name "Net-(U9-VIN-)") (class "Default")
      (node (ref "R28") (pin "2") (pinfunction "2_2") (pintype "passive"))
      (node (ref "R29") (pin "1") (pinfunction "1_1") (pintype "passive"))
      (node (ref "U9") (pin "3") (pinfunction "VIN-_3") (pintype "bidirectional"))
    )
    (net (code "86") (name "Net-(U12-A0)") (class "Default")
      (node (ref "JP3") (pin "2") (pinfunction "2_2") (pintype "passive"))
      (node (ref "U12") (pin "7") (pinfunction "A0_7") (pintype "bidirectional"))
    )
    (net (code "87") (name "Net-(U12-A1)") (class "Default")
      (node (ref "JP4") (pin "2") (pinfunction "2_2") (pintype "passive"))
      (node (ref "U12") (pin "6") (pinfunction "A1_6") (pintype "bidirectional"))
    )
    (net (code "88") (name "Net-(U12-A2)") (class "Default")
      (node (ref "JP5") (pin "2") (pinfunction "2_2") (pintype "passive"))
      (node (ref "U12") (pin "5") (pinfunction "A2_5") (pintype "bidirectional"))
    )
    (net (code "89") (name "Net-(U17-A12{slash}D+)") (class "Default")
      (node (ref "R53") (pin "2") (pinfunction "2_2") (pintype "passive"))
      (node (ref "U17") (pin "A12") (pinfunction "A12/D+_A12") (pintype "bidirectional"))
    )
    (net (code "90") (name "OA1+") (class "Default")
      (node (ref "D5") (pin "A") (pinfunction "ANODE_A") (pintype "passive"))
      (node (ref "R18") (pin "1") (pinfunction "1_1") (pintype "passive"))
      (node (ref "R82") (pin "1") (pinfunction "1_1") (pintype "passive"))
      (node (ref "R83") (pin "1") (pinfunction "1_1") (pintype "passive"))
    )
    (net (code "91") (name "OA1-") (class "Default")
      (node (ref "R20") (pin "1") (pinfunction "1_1") (pintype "passive"))
      (node (ref "R54") (pin "1") (pinfunction "1_1") (pintype "passive"))
      (node (ref "R55") (pin "1") (pinfunction "1_1") (pintype "passive"))
    )
    (net (code "92") (name "OA2+") (class "Default")
      (node (ref "D6") (pin "A") (pinfunction "ANODE_A") (pintype "passive"))
      (node (ref "R26") (pin "1") (pinfunction "1_1") (pintype "passive"))
      (node (ref "R86") (pin "1") (pinfunction "1_1") (pintype "passive"))
      (node (ref "R87") (pin "1") (pinfunction "1_1") (pintype "passive"))
    )
    (net (code "93") (name "OA2-") (class "Default")
      (node (ref "R28") (pin "1") (pinfunction "1_1") (pintype "passive"))
      (node (ref "R84") (pin "1") (pinfunction "1_1") (pintype "passive"))
      (node (ref "R85") (pin "1") (pinfunction "1_1") (pintype "passive"))
    )
    (net (code "94") (name "PA8") (class "Default")
      (node (ref "R42") (pin "2") (pinfunction "2_2") (pintype "passive"))
      (node (ref "R80") (pin "1") (pinfunction "1_1") (pintype "passive"))
      (node (ref "U17") (pin "A8") (pinfunction "A8_A8") (pintype "bidirectional"))
    )
    (net (code "95") (name "PA10") (class "Default")
      (node (ref "R46") (pin "2") (pinfunction "2_2") (pintype "passive"))
      (node (ref "R81") (pin "1") (pinfunction "1_1") (pintype "passive"))
      (node (ref "U17") (pin "A10") (pinfunction "A10_A10") (pintype "bidirectional"))
    )
    (net (code "96") (name "PB2") (class "Default")
      (node (ref "R76") (pin "1") (pinfunction "1_1") (pintype "passive"))
      (node (ref "U17") (pin "B2") (pinfunction "B2_B2") (pintype "bidirectional"))
      (node (ref "U18") (pin "6") (pinfunction "SEL_6") (pintype "bidirectional"))
    )
    (net (code "97") (name "PB5") (class "Default")
      (node (ref "JP6") (pin "3") (pinfunction "3_3") (pintype "passive"))
      (node (ref "JP7") (pin "1") (pinfunction "1_1") (pintype "passive"))
      (node (ref "R49") (pin "1") (pinfunction "1_1") (pintype "passive"))
      (node (ref "U15") (pin "6") (pinfunction "SEL_6") (pintype "bidirectional"))
      (node (ref "U17") (pin "B5") (pinfunction "B5_B5") (pintype "bidirectional"))
    )
    (net (code "98") (name "S1") (class "Default")
      (node (ref "S1") (pin "1") (pinfunction "1_1") (pintype "passive"))
      (node (ref "S1") (pin "2") (pinfunction "2_2") (pintype "passive"))
      (node (ref "U17") (pin "B9") (pinfunction "B9_B9") (pintype "bidirectional"))
    )
    (net (code "99") (name "S2") (class "Default")
      (node (ref "S2") (pin "1") (pinfunction "1_1") (pintype "passive"))
      (node (ref "S2") (pin "2") (pinfunction "2_2") (pintype "passive"))
      (node (ref "U17") (pin "C13") (pinfunction "C13_C13") (pintype "bidirectional"))
    )
    (net (code "100") (name "SCL-TX") (class "Default")
      (node (ref "JP1") (pin "2") (pinfunction "2_2") (pintype "passive"))
      (node (ref "JP2") (pin "2") (pinfunction "2_2") (pintype "passive"))
      (node (ref "LCD1") (pin "3=SCL") (pinfunction "SCL_3=SCL") (pintype "bidirectional"))
      (node (ref "U12") (pin "2") (pinfunction "SCL_2") (pintype "bidirectional"))
      (node (ref "U17") (pin "B10") (pinfunction "B10_B10") (pintype "bidirectional"))
    )
    (net (code "101") (name "SDA-RX") (class "Default")
      (node (ref "JP1") (pin "3") (pinfunction "3_3") (pintype "passive"))
      (node (ref "JP2") (pin "1") (pinfunction "1_1") (pintype "passive"))
      (node (ref "LCD1") (pin "4-SDA") (pinfunction "SDA_4-SDA") (pintype "bidirectional"))
      (node (ref "U12") (pin "1") (pinfunction "SDA_1") (pintype "bidirectional"))
      (node (ref "U17") (pin "B11") (pinfunction "B11_B11") (pintype "bidirectional"))
    )
    (net (code "102") (name "unconnected-(U12-OS-Pad3)") (class "Default")
      (node (ref "U12") (pin "3") (pinfunction "OS_3") (pintype "bidirectional"))
    )
    (net (code "103") (name "unconnected-(U17-A13-PadDIO)") (class "Default")
      (node (ref "U17") (pin "DIO") (pinfunction "A13_DIO") (pintype "bidirectional"))
    )
    (net (code "104") (name "unconnected-(U17-A14-PadDCLK)") (class "Default")
      (node (ref "U17") (pin "DCLK") (pinfunction "A14_DCLK") (pintype "bidirectional"))
    )
    (net (code "105") (name "unconnected-(U17-PadB12)") (class "Default")
      (node (ref "U17") (pin "B12") (pinfunction "B12_B12") (pintype "bidirectional"))
    )
    (net (code "106") (name "unconnected-(U17-PadRST)") (class "Default")
      (node (ref "U17") (pin "RST") (pinfunction "RST_RST") (pintype "bidirectional"))
    )
    (net (code "107") (name "unconnected-(U17-VB-PadVBAT)") (class "Default")
      (node (ref "U17") (pin "VBAT") (pinfunction "VB_VBAT") (pintype "bidirectional"))
    )
  )
)
